# Charger_Control_Board_rev9.net
KiCad netlist of a schematic drawn in EAGLE
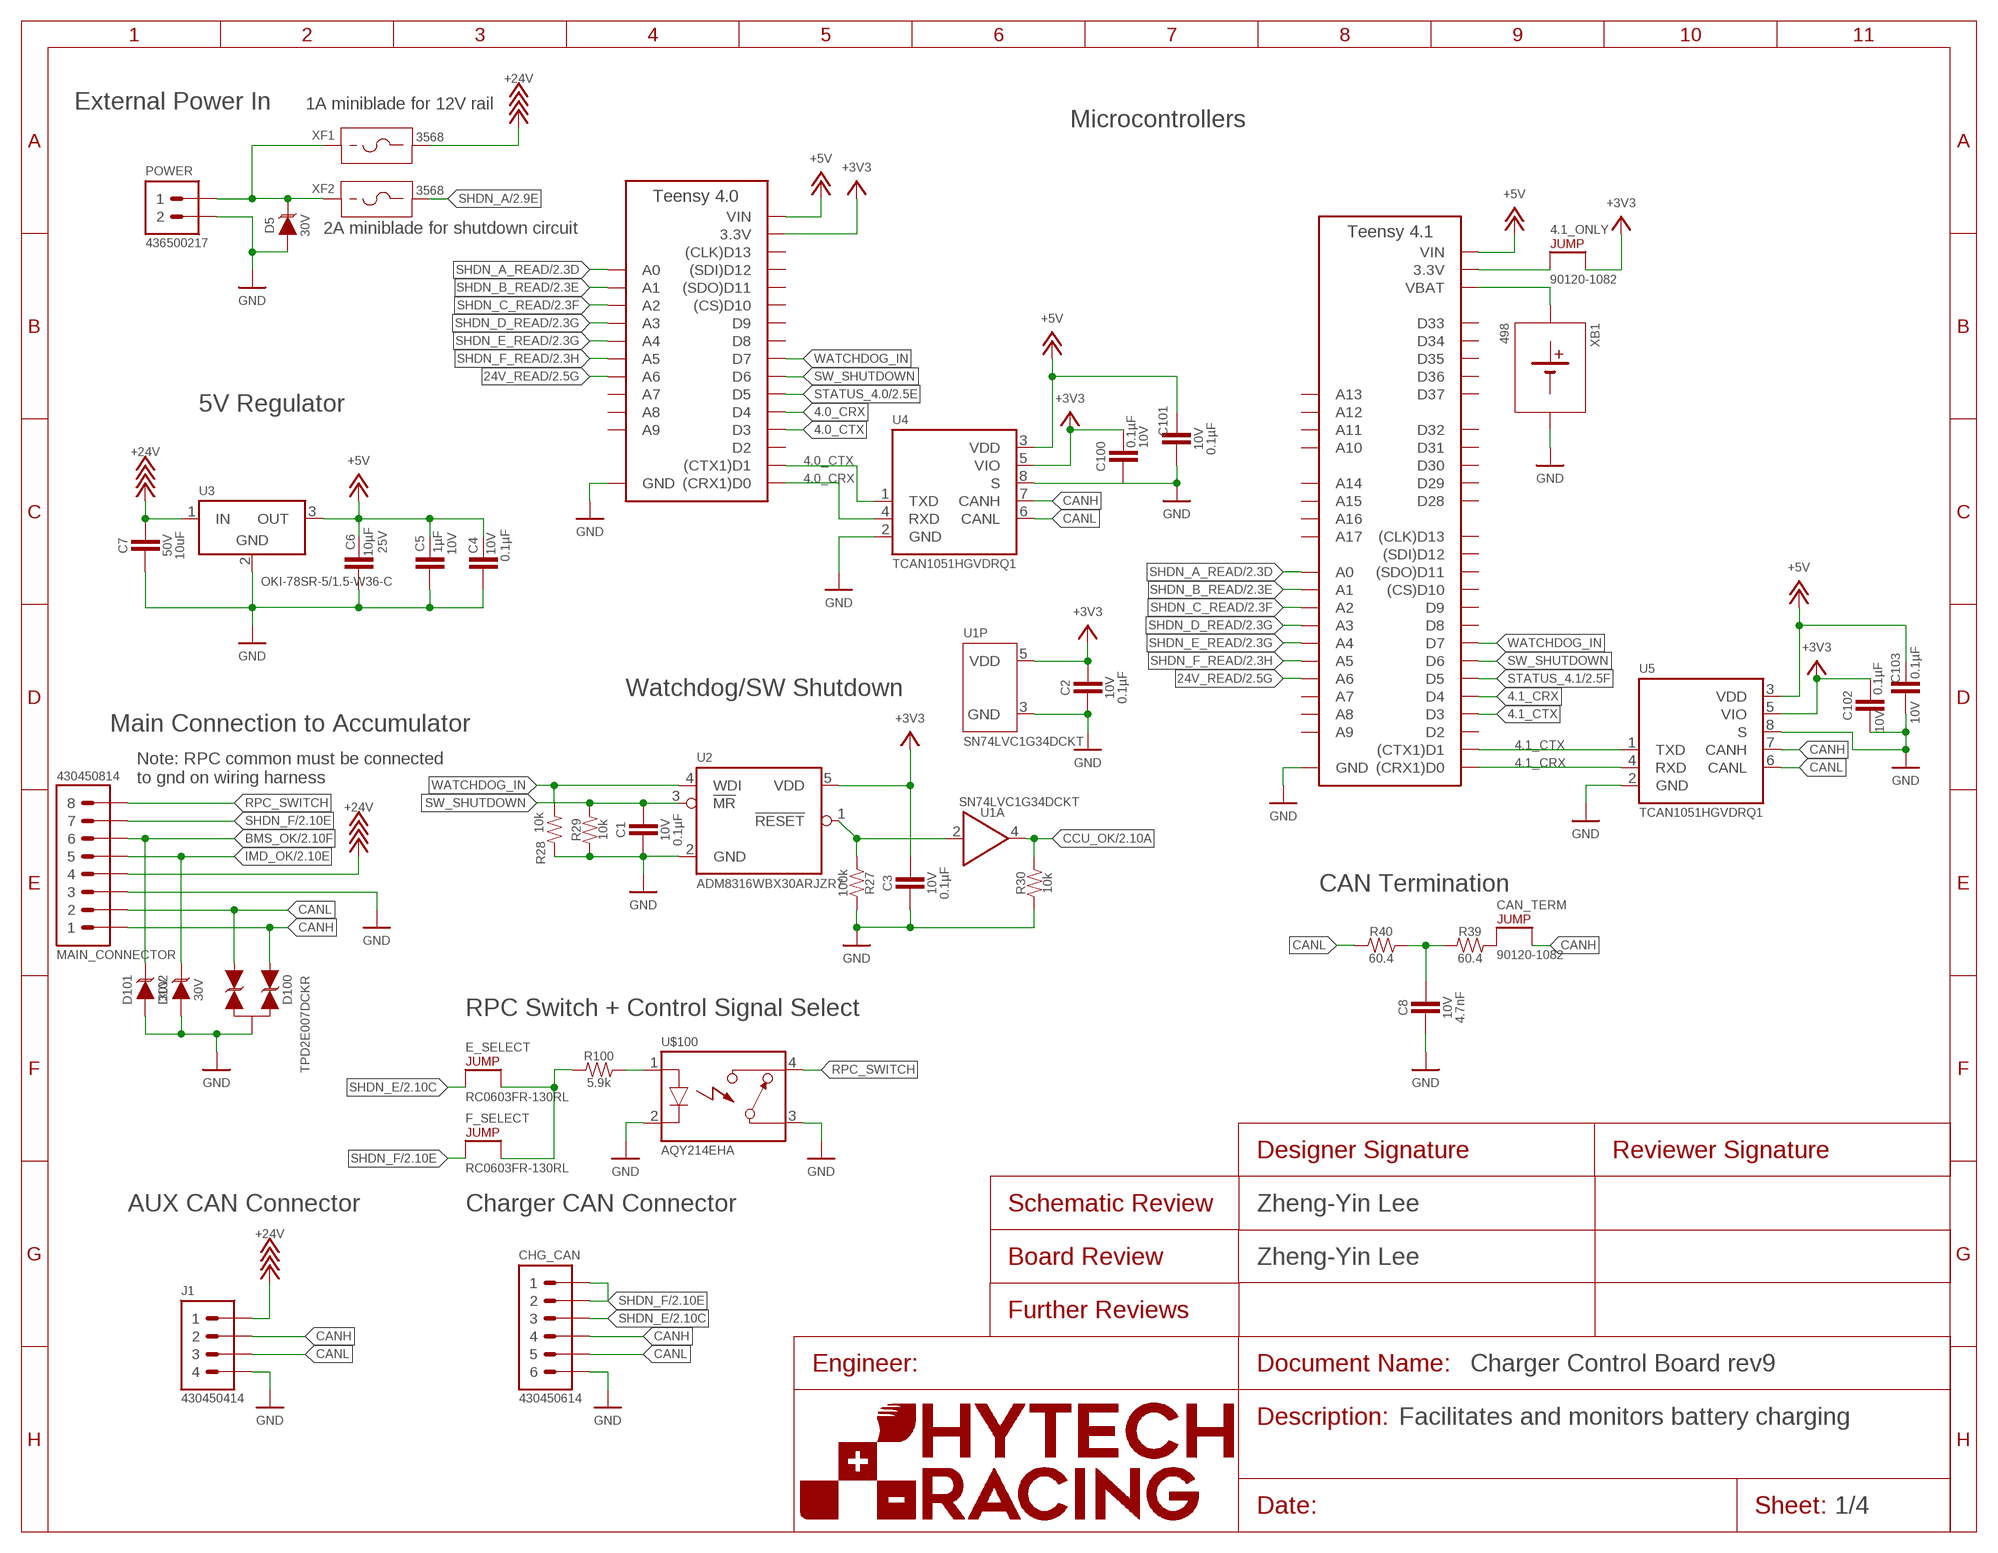
[diagram p0: schematic, sheet 1]
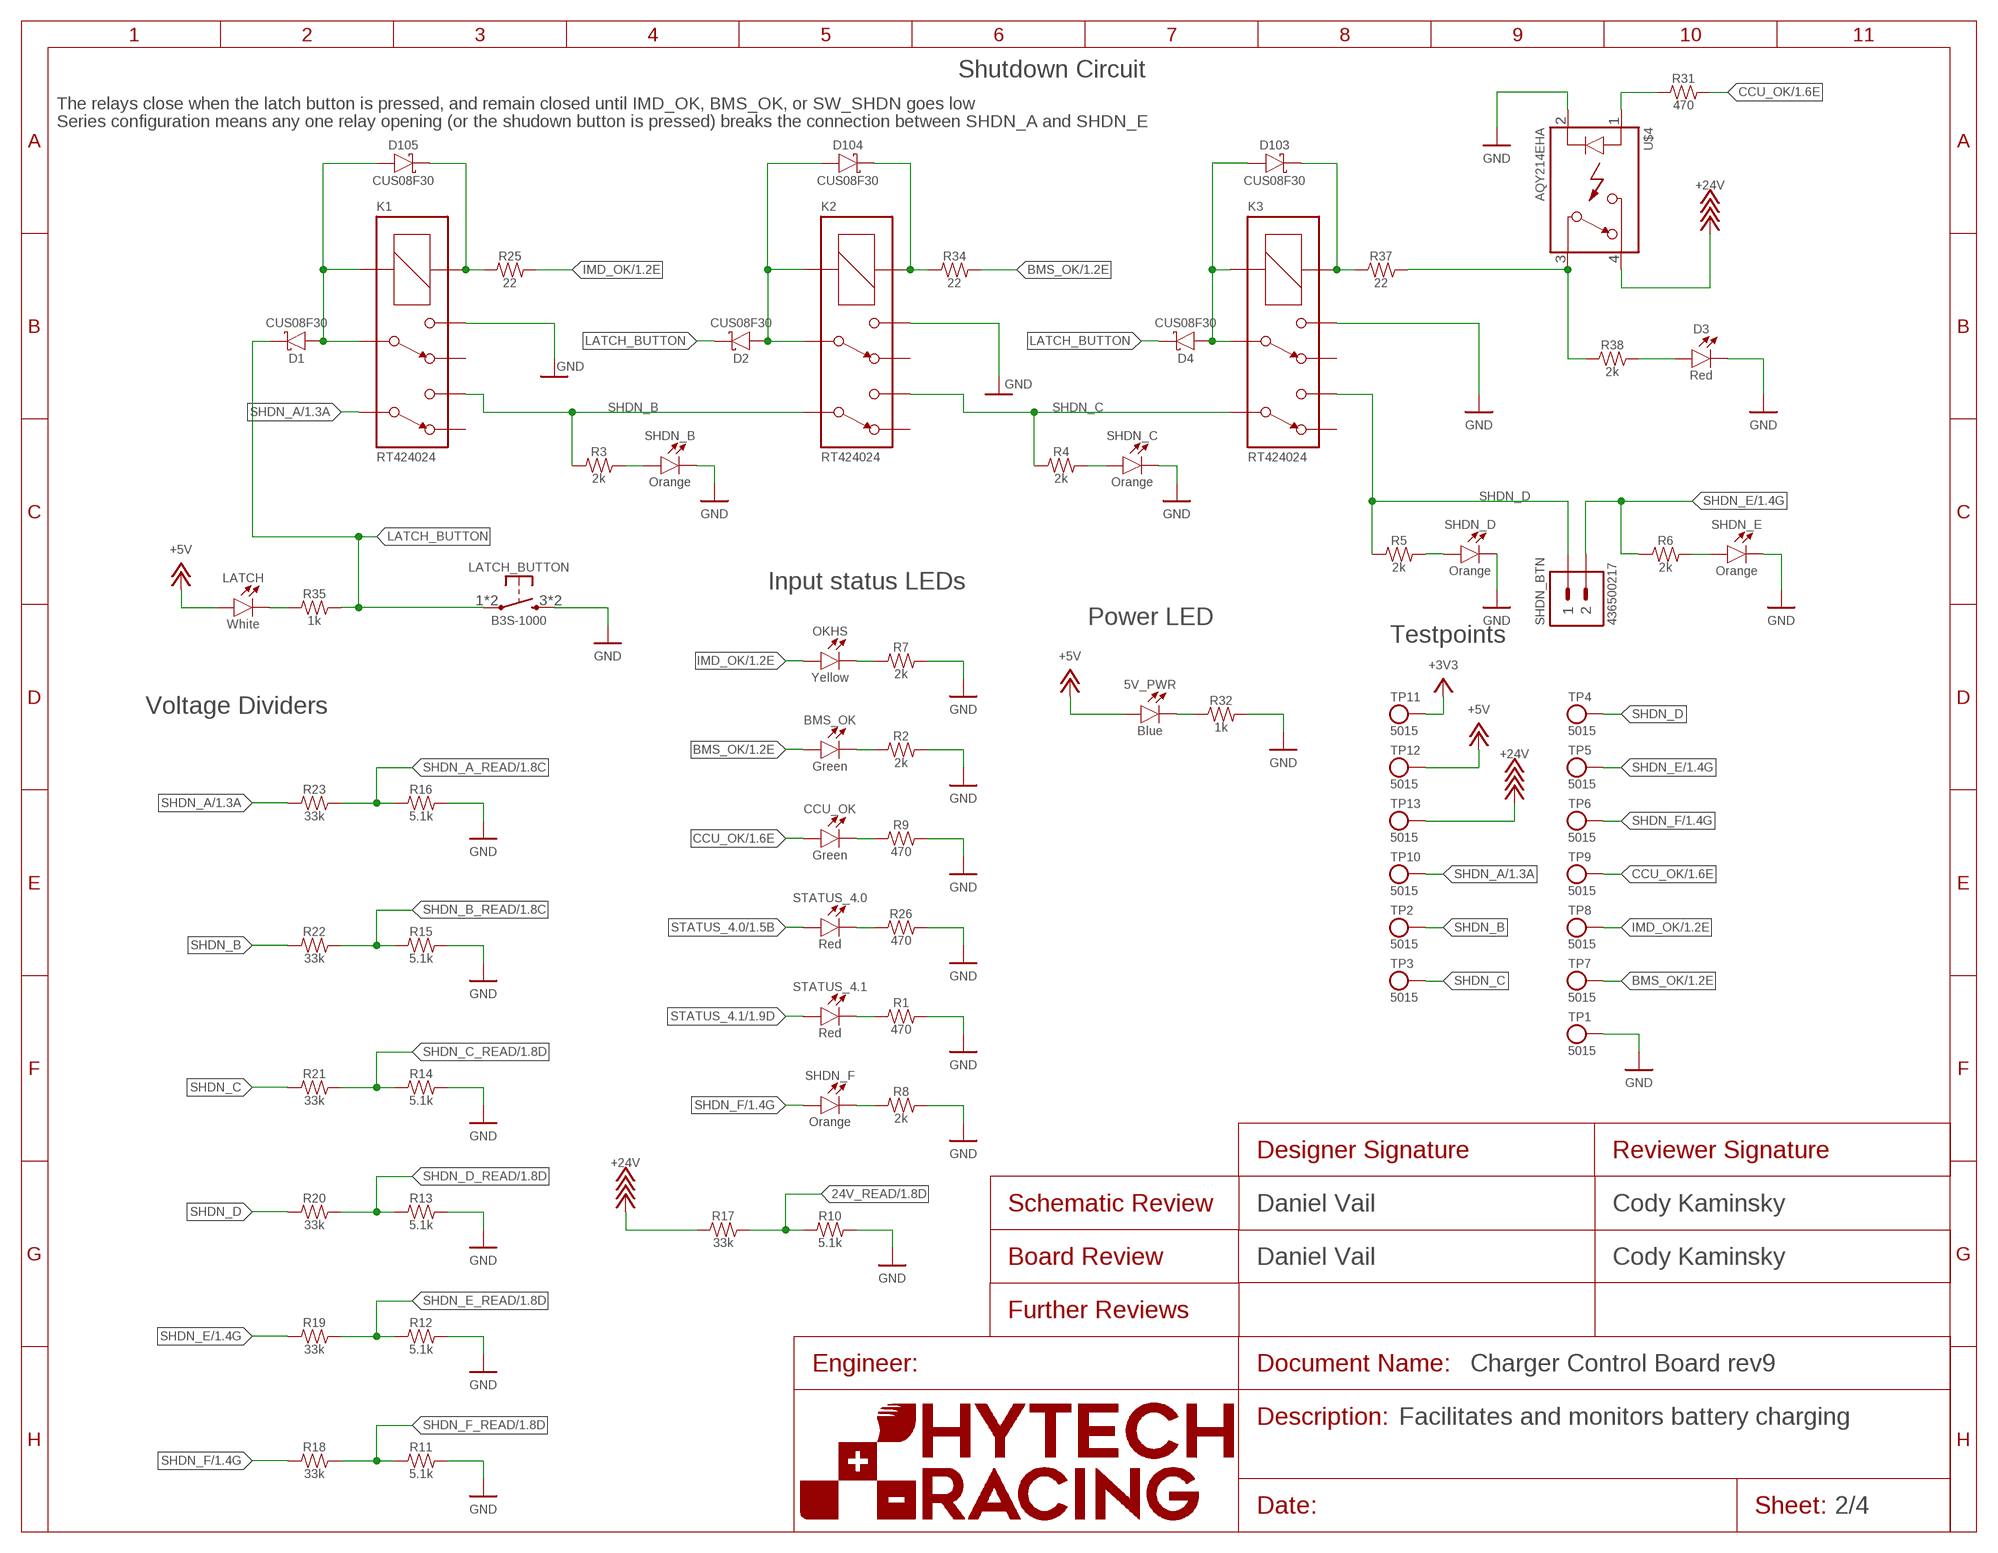
[diagram p1: schematic, sheet 2]
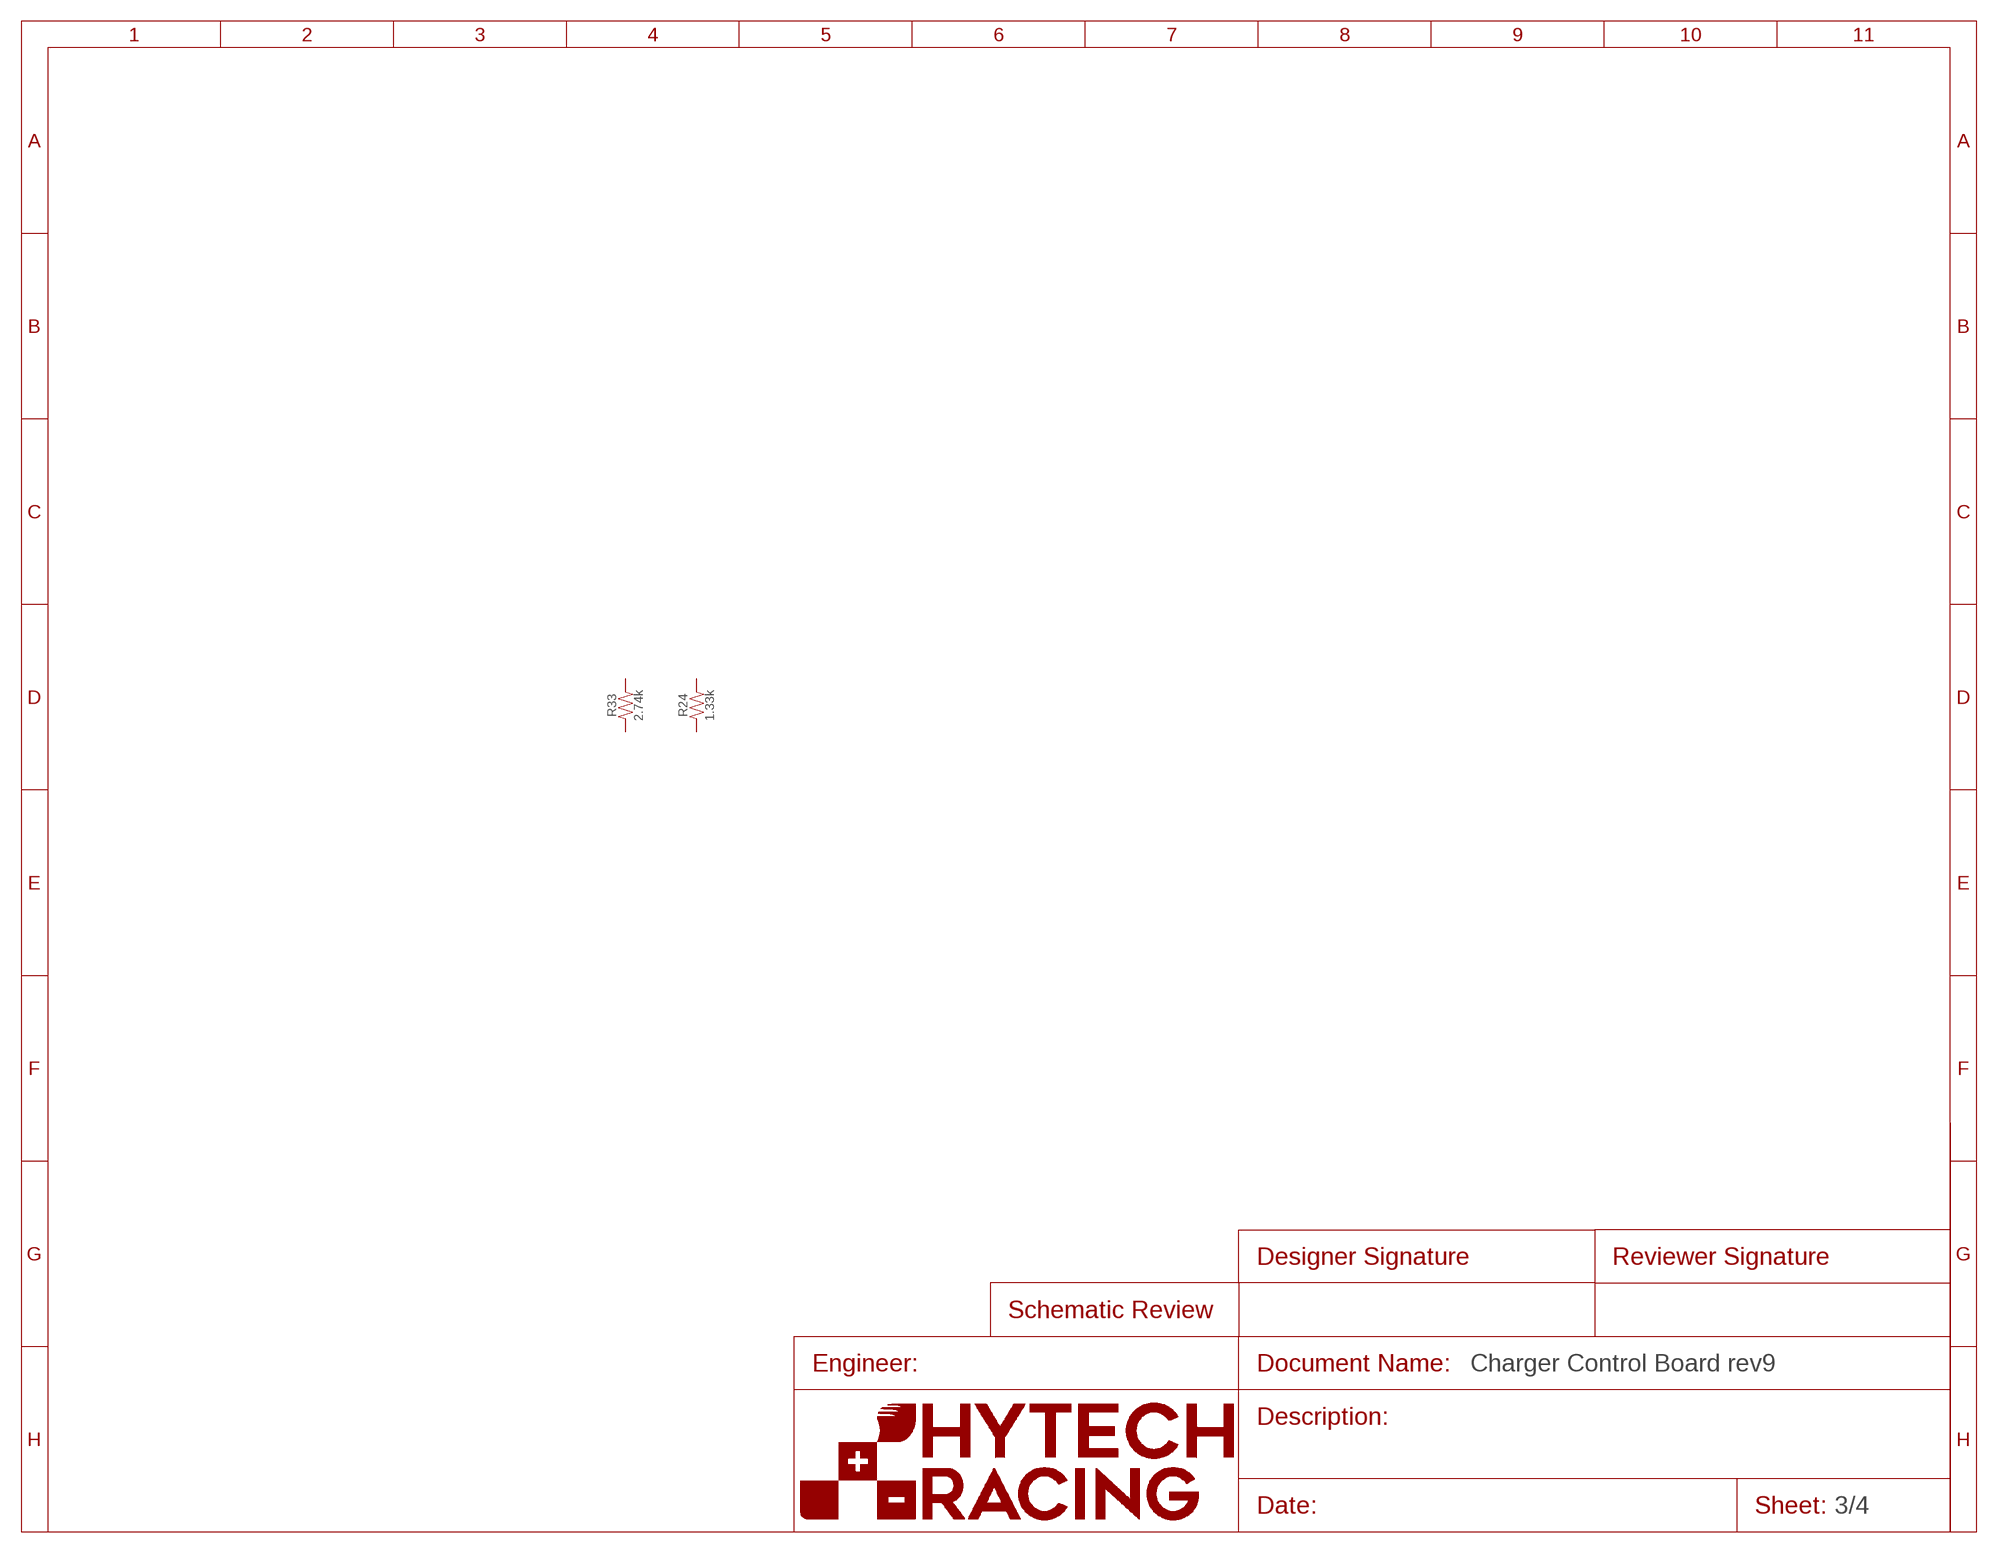
[diagram p2: schematic, sheet 3]
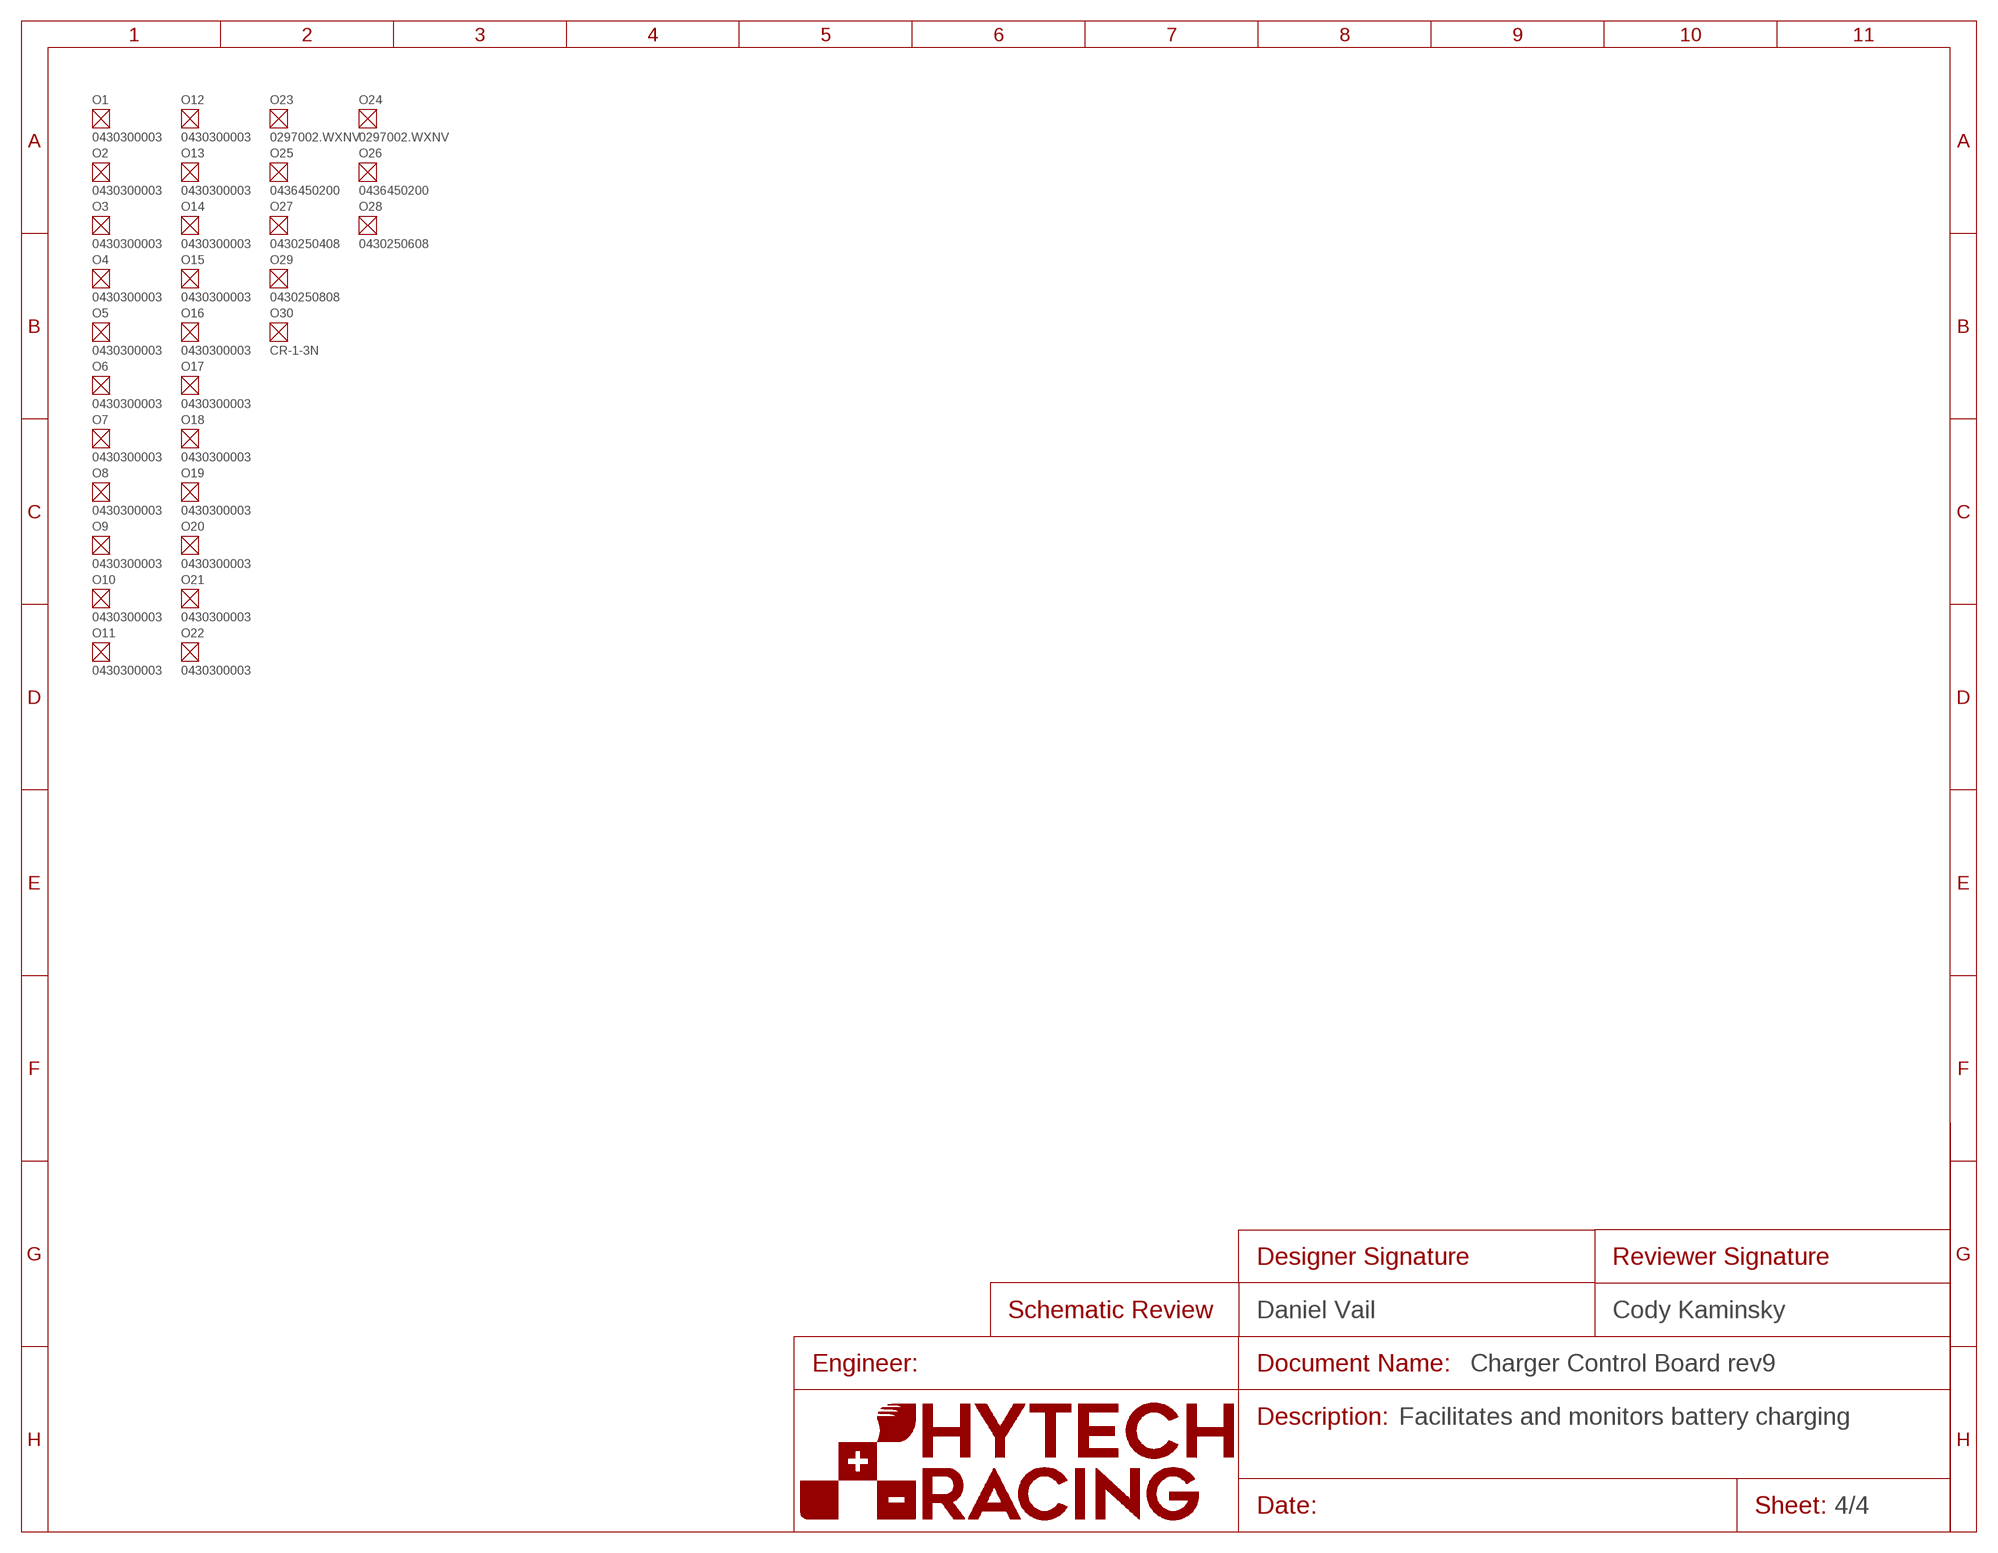
[diagram p3: schematic, sheet 4]

(export (version "E")
  (design (tool "Eeschema 10.0.6"))
  (components
    (comp (ref "4.1_ONLY")
      (value "JUMPER__1X02")
      (footprint "eagle-import:1X02")
      (fields (field (name "MANUFACTURER") "Molex") (field (name "MPN") "90120-1082 "))
      (libsource (lib "eagle-import") (part "JUMPER_?_1X02"))
    )
    (comp (ref "A1")
      (value "TEENSY_4.1")
      (footprint "eagle-import:TEENSY_LONG_EXT")
      (libsource (lib "eagle-import") (part "TEENSY_4.1"))
    )
    (comp (ref "A2")
      (value "TEENSY_4.0TH")
      (footprint "eagle-import:TEENSY_SHORT")
      (libsource (lib "eagle-import") (part "TEENSY_4.0TH"))
    )
    (comp (ref "C1")
      (value "CAPACITOR_0603_10V_0.1UF")
      (footprint "eagle-import:0603-CAP")
      (fields
        (field (name "CAPACITANCE") "0.1µF")
        (field (name "MANUFACTURER") "Vishay Vitramon")
        (field (name "MPN") "VJ0603Y104JXQPW1BC")
        (field (name "TOLERANCE") "5%")
        (field (name "VOLTAGE") "10V")
      )
      (libsource (lib "eagle-import") (part "CAPACITOR_?_060310V_0.1UF"))
    )
    (comp (ref "C2")
      (value "CAPACITOR_0603_10V_0.1UF")
      (footprint "eagle-import:0603-CAP")
      (fields
        (field (name "CAPACITANCE") "0.1µF")
        (field (name "MANUFACTURER") "Vishay Vitramon")
        (field (name "MPN") "VJ0603Y104JXQPW1BC")
        (field (name "TOLERANCE") "5%")
        (field (name "VOLTAGE") "10V")
      )
      (libsource (lib "eagle-import") (part "CAPACITOR_?_060310V_0.1UF"))
    )
    (comp (ref "C3")
      (value "CAPACITOR_0603_10V_0.1UF")
      (footprint "eagle-import:0603-CAP")
      (fields
        (field (name "CAPACITANCE") "0.1µF")
        (field (name "MANUFACTURER") "Vishay Vitramon")
        (field (name "MPN") "VJ0603Y104JXQPW1BC")
        (field (name "TOLERANCE") "5%")
        (field (name "VOLTAGE") "10V")
      )
      (libsource (lib "eagle-import") (part "CAPACITOR_?_060310V_0.1UF"))
    )
    (comp (ref "C4")
      (value "CAPACITOR_0603_10V_0.1UF")
      (footprint "eagle-import:0603-CAP")
      (fields
        (field (name "CAPACITANCE") "0.1µF")
        (field (name "MANUFACTURER") "Vishay Vitramon")
        (field (name "MPN") "VJ0603Y104JXQPW1BC")
        (field (name "TOLERANCE") "5%")
        (field (name "VOLTAGE") "10V")
      )
      (libsource (lib "eagle-import") (part "CAPACITOR_?_060310V_0.1UF"))
    )
    (comp (ref "C5")
      (value "CAPACITOR_0603_10V_1UF")
      (footprint "eagle-import:0603-CAP")
      (fields
        (field (name "CAPACITANCE") "1µF")
        (field (name "MANUFACTURER") "Yageo")
        (field (name "MPN") "CC0603KRX7R6BB105")
        (field (name "TOLERANCE") "10%")
        (field (name "VOLTAGE") "10V")
      )
      (libsource (lib "eagle-import") (part "CAPACITOR_?_060310V_1UF"))
    )
    (comp (ref "C6")
      (value "CAPACITOR_0603_25V_10UF")
      (footprint "eagle-import:0603-CAP")
      (fields
        (field (name "CAPACITANCE") "10µF")
        (field (name "MANUFACTURER") "Murata Electronics")
        (field (name "MPN") "GRM188R61E106MA73D")
        (field (name "TOLERANCE") "20%")
        (field (name "VOLTAGE") "25V")
      )
      (libsource (lib "eagle-import") (part "CAPACITOR_?_060325V_10UF"))
    )
    (comp (ref "C7")
      (value "CAPACITOR_0805_50V_10UF")
      (footprint "eagle-import:0805-CAP")
      (fields
        (field (name "CAPACITANCE") "10uF")
        (field (name "MANUFACTURER") "Murata")
        (field (name "MPN") " GRM21BR61H106KE43L")
        (field (name "TOLERANCE") "10%")
        (field (name "VOLTAGE") "50V")
      )
      (libsource (lib "eagle-import") (part "CAPACITOR_?_080550V_10UF"))
    )
    (comp (ref "C8")
      (value "CAPACITOR_0603_10V_4.7NF")
      (footprint "eagle-import:0603-CAP")
      (fields
        (field (name "CAPACITANCE") "4.7nF")
        (field (name "MANUFACTURER") "Würth Elektronik")
        (field (name "MPN") "885012206012")
        (field (name "TOLERANCE") "10%")
        (field (name "VOLTAGE") "10V")
      )
      (libsource (lib "eagle-import") (part "CAPACITOR_?_060310V_4.7NF"))
    )
    (comp (ref "C100")
      (value "CAPACITOR_0603_10V_0.1UF")
      (footprint "eagle-import:0603-CAP")
      (fields
        (field (name "CAPACITANCE") "0.1µF")
        (field (name "MANUFACTURER") "Vishay Vitramon")
        (field (name "MPN") "VJ0603Y104JXQPW1BC")
        (field (name "TOLERANCE") "5%")
        (field (name "VOLTAGE") "10V")
      )
      (libsource (lib "eagle-import") (part "CAPACITOR_?_060310V_0.1UF"))
    )
    (comp (ref "C101")
      (value "CAPACITOR_0603_10V_0.1UF")
      (footprint "eagle-import:0603-CAP")
      (fields
        (field (name "CAPACITANCE") "0.1µF")
        (field (name "MANUFACTURER") "Vishay Vitramon")
        (field (name "MPN") "VJ0603Y104JXQPW1BC")
        (field (name "TOLERANCE") "5%")
        (field (name "VOLTAGE") "10V")
      )
      (libsource (lib "eagle-import") (part "CAPACITOR_?_060310V_0.1UF"))
    )
    (comp (ref "C102")
      (value "CAPACITOR_0603_10V_0.1UF")
      (footprint "eagle-import:0603-CAP")
      (fields
        (field (name "CAPACITANCE") "0.1µF")
        (field (name "MANUFACTURER") "Vishay Vitramon")
        (field (name "MPN") "VJ0603Y104JXQPW1BC")
        (field (name "TOLERANCE") "5%")
        (field (name "VOLTAGE") "10V")
      )
      (libsource (lib "eagle-import") (part "CAPACITOR_?_060310V_0.1UF"))
    )
    (comp (ref "C103")
      (value "CAPACITOR_0603_10V_0.1UF")
      (footprint "eagle-import:0603-CAP")
      (fields
        (field (name "CAPACITANCE") "0.1µF")
        (field (name "MANUFACTURER") "Vishay Vitramon")
        (field (name "MPN") "VJ0603Y104JXQPW1BC")
        (field (name "TOLERANCE") "5%")
        (field (name "VOLTAGE") "10V")
      )
      (libsource (lib "eagle-import") (part "CAPACITOR_?_060310V_0.1UF"))
    )
    (comp (ref "CAN_TERM")
      (value "JUMPER__1X02")
      (footprint "eagle-import:1X02")
      (fields (field (name "MANUFACTURER") "Molex") (field (name "MPN") "90120-1082 "))
      (libsource (lib "eagle-import") (part "JUMPER_?_1X02"))
    )
    (comp (ref "CHG_CAN")
      (value "CONNECTOR-6_MF_T_V_")
      (footprint "eagle-import:MOLEX_MICROFIT_PTH_VERTICAL_06_DUAL")
      (fields (field (name "MPN") "430450614") (field (name "MANUFACTURER") "MOLEX"))
      (libsource (lib "eagle-import") (part "CONNECTOR-6_?_MF_T_V"))
    )
    (comp (ref "D5")
      (value "TVS_DO-214AA_30V")
      (footprint "eagle-import:DO-214AA")
      (fields
        (field (name "MANUFACTURER") "Bourns Inc.")
        (field (name "MPN") " 1.5SMBJ30A")
        (field (name "VOLTAGE") "30V")
      )
      (libsource (lib "eagle-import") (part "TVS_?_DO-214AA30V"))
    )
    (comp (ref "D100")
      (value "TVS_BIDIRECTIONAL_DUAL")
      (footprint "eagle-import:SC-70-3")
      (fields (field (name "MPN") "TPD2E007DCKR") (field (name "MANUFACTURER") "Texas Instruments"))
      (libsource (lib "eagle-import") (part "TVS_BIDIRECTIONAL_DUAL"))
    )
    (comp (ref "D101")
      (value "TVS_DO-214AA_30V")
      (footprint "eagle-import:DO-214AA")
      (fields
        (field (name "MANUFACTURER") "Bourns Inc.")
        (field (name "MPN") " 1.5SMBJ30A")
        (field (name "VOLTAGE") "30V")
      )
      (libsource (lib "eagle-import") (part "TVS_?_DO-214AA30V"))
    )
    (comp (ref "D102")
      (value "TVS_DO-214AA_30V")
      (footprint "eagle-import:DO-214AA")
      (fields
        (field (name "MANUFACTURER") "Bourns Inc.")
        (field (name "MPN") " 1.5SMBJ30A")
        (field (name "VOLTAGE") "30V")
      )
      (libsource (lib "eagle-import") (part "TVS_?_DO-214AA30V"))
    )
    (comp (ref "E_SELECT")
      (value "JUMPER_0603_")
      (footprint "eagle-import:0603-RES")
      (fields (field (name "MPN") "RC0603FR-130RL") (field (name "MANUFACTURER") "YAGEO"))
      (libsource (lib "eagle-import") (part "JUMPER_?_0603"))
    )
    (comp (ref "F_SELECT")
      (value "JUMPER_0603_")
      (footprint "eagle-import:0603-RES")
      (fields (field (name "MPN") "RC0603FR-130RL") (field (name "MANUFACTURER") "YAGEO"))
      (libsource (lib "eagle-import") (part "JUMPER_?_0603"))
    )
    (comp (ref "J1")
      (value "CONNECTOR-4_μF_T_V_BLACK")
      (footprint "eagle-import:MOLEX_MICROFIT_PTH_VERTICAL_04_DUAL")
      (fields (field (name "MANUFACTURER") "Molex") (field (name "MPN") "430450414"))
      (libsource (lib "eagle-import") (part "CONNECTOR-4_?_μF_T_VBLACK"))
    )
    (comp (ref "MAIN_CONNECTOR")
      (value "CONNECTOR-8_MF_T_V_")
      (footprint "eagle-import:MOLEX_MICROFIT_PTH_VERTICAL_08_DUAL")
      (fields (field (name "MPN") "430450814") (field (name "MANUFACTURER") "MOLEX"))
      (libsource (lib "eagle-import") (part "CONNECTOR-8_?_MF_T_V"))
    )
    (comp (ref "POWER")
      (value "CONNECTOR-2_μF_T_V_")
      (footprint "eagle-import:MOLEX_MICROFIT_PTH_VERTICAL_02_DUAL")
      (fields (field (name "MANUFACTURER") "Molex") (field (name "MPN") "436500217"))
      (libsource (lib "eagle-import") (part "CONNECTOR-2_?_μF_T_VBLACK"))
    )
    (comp (ref "R27")
      (value "RESISTOR_0603_100K")
      (footprint "eagle-import:0603-RES")
      (fields
        (field (name "MANUFACTURER") "Yageo")
        (field (name "MPN") "RC0603FR-07100KL")
        (field (name "POWER") "0.1W")
        (field (name "RESISTANCE") "100k")
      )
      (libsource (lib "eagle-import") (part "RESISTOR_?_0603100K"))
    )
    (comp (ref "R28")
      (value "RESISTOR_0603_10K")
      (footprint "eagle-import:0603-RES")
      (fields
        (field (name "MANUFACTURER") "Panasonic Electronic Components")
        (field (name "MPN") "ERA-3ARB103V")
        (field (name "POWER") "0.1W")
        (field (name "RESISTANCE") "10k")
      )
      (libsource (lib "eagle-import") (part "RESISTOR_?_060310K"))
    )
    (comp (ref "R29")
      (value "RESISTOR_0603_10K")
      (footprint "eagle-import:0603-RES")
      (fields
        (field (name "MANUFACTURER") "Panasonic Electronic Components")
        (field (name "MPN") "ERA-3ARB103V")
        (field (name "POWER") "0.1W")
        (field (name "RESISTANCE") "10k")
      )
      (libsource (lib "eagle-import") (part "RESISTOR_?_060310K"))
    )
    (comp (ref "R30")
      (value "RESISTOR_0603_10K")
      (footprint "eagle-import:0603-RES")
      (fields
        (field (name "MANUFACTURER") "Panasonic Electronic Components")
        (field (name "MPN") "ERA-3ARB103V")
        (field (name "POWER") "0.1W")
        (field (name "RESISTANCE") "10k")
      )
      (libsource (lib "eagle-import") (part "RESISTOR_?_060310K"))
    )
    (comp (ref "R39")
      (value "RESISTOR_0603_60.4")
      (footprint "eagle-import:0603-RES")
      (fields
        (field (name "MANUFACTURER") "Yageo")
        (field (name "MPN") "RC0603FR-0760R4L")
        (field (name "POWER") "0.1W")
        (field (name "RESISTANCE") "60.4")
      )
      (libsource (lib "eagle-import") (part "RESISTOR_?_060360.4"))
    )
    (comp (ref "R40")
      (value "RESISTOR_0603_60.4")
      (footprint "eagle-import:0603-RES")
      (fields
        (field (name "MANUFACTURER") "Yageo")
        (field (name "MPN") "RC0603FR-0760R4L")
        (field (name "POWER") "0.1W")
        (field (name "RESISTANCE") "60.4")
      )
      (libsource (lib "eagle-import") (part "RESISTOR_?_060360.4"))
    )
    (comp (ref "R100")
      (value "RESISTOR_0603_5.9K")
      (footprint "eagle-import:0603-RES")
      (fields
        (field (name "MANUFACTURER") "Panasonic Electronic Components")
        (field (name "MPN") "ERA-3AEB5901V")
        (field (name "POWER") "0.1W")
        (field (name "RESISTANCE") "5.9k")
      )
      (libsource (lib "eagle-import") (part "RESISTOR_?_06035.9K"))
    )
    (comp (ref "U$100")
      (value "RELAY_SOLIDSTATE_NO_DIP-4")
      (footprint "eagle-import:DIP-4")
      (fields (field (name "MPN") "AQY214EHA") (field (name "MANUFACTURER") "Panasonic"))
      (libsource (lib "eagle-import") (part "RELAY_SOLIDSTATE_NO_DIP-4"))
    )
    (comp (ref "U1")
      (value "LOGICGATE_BUFFER")
      (footprint "eagle-import:SC-70-5")
      (fields (field (name "MANUFACTURER") "Texas Instruments"))
      (libsource (lib "eagle-import") (part "LOGICGATE_BUFFER"))
    )
    (comp (ref "U2")
      (value "ADM8316WBX30")
      (footprint "eagle-import:SOT-23-5")
      (fields (field (name "MANUFACTURER") "Analog Devices Inc.") (field (name "MPN") "ADM8316WBX30ARJZR7"))
      (libsource (lib "eagle-import") (part "ADM8316WBX30"))
    )
    (comp (ref "U3")
      (value "VOLTAGE_REGULATOR_MODULE_OKI-78SR_5V")
      (footprint "eagle-import:OKI-78SR")
      (fields
        (field (name "MANUFACTURER") "Murata Power Solutions Inc.")
        (field (name "MPN") "OKI-78SR-5/1.5-W36-C")
      )
      (libsource (lib "eagle-import") (part "VOLTAGE_REGULATOR_MODULE_?_OKI-78SR5V"))
    )
    (comp (ref "U4")
      (value "TCAN1051HQV-Q1")
      (footprint "eagle-import:SOIC-08(NARROW,0.15_)")
      (fields (field (name "MANUFACTURER") "Texas Instruments") (field (name "MPN") "TCAN1051HGVDRQ1"))
      (libsource (lib "eagle-import") (part "TCAN1051V-Q1HQ"))
    )
    (comp (ref "U5")
      (value "TCAN1051HQV-Q1")
      (footprint "eagle-import:SOIC-08(NARROW,0.15_)")
      (fields (field (name "MANUFACTURER") "Texas Instruments") (field (name "MPN") "TCAN1051HGVDRQ1"))
      (libsource (lib "eagle-import") (part "TCAN1051V-Q1HQ"))
    )
    (comp (ref "XB1")
      (value "BATTERY_HOLDER_KEYSTONE_498")
      (footprint "eagle-import:498")
      (fields (field (name "MPN") "498") (field (name "MANUFACTURER") "Keystone Electronics"))
      (libsource (lib "eagle-import") (part "BATTERY_HOLDER_KEYSTONE_498"))
    )
    (comp (ref "XF1")
      (value "FUSE_HOLDER_MINIBLADEPTH")
      (footprint "eagle-import:3568")
      (fields (field (name "MANUFACTURER") "Keystone") (field (name "MPN") "3568"))
      (libsource (lib "eagle-import") (part "FUSE_HOLDER_PTHMINIBLADE"))
    )
    (comp (ref "XF2")
      (value "FUSE_HOLDER_MINIBLADEPTH")
      (footprint "eagle-import:3568")
      (fields (field (name "MANUFACTURER") "Keystone") (field (name "MPN") "3568"))
      (libsource (lib "eagle-import") (part "FUSE_HOLDER_PTHMINIBLADE"))
    )
    (comp (ref "5V_PWR")
      (value "LED_0603_BLUE")
      (footprint "eagle-import:0603-LED")
      (fields
        (field (name "COLOR") "Blue")
        (field (name "MANUFACTURER") "Kingbright")
        (field (name "MPN") "APT1608VBC/D")
      )
      (libsource (lib "eagle-import") (part "LED_?_0603BLUE"))
    )
    (comp (ref "BMS_OK")
      (value "LED_0603_GREEN")
      (footprint "eagle-import:0603-LED")
      (fields
        (field (name "COLOR") "Green")
        (field (name "MANUFACTURER") "Kingbright")
        (field (name "MPN") "APT1608ZGCK")
      )
      (libsource (lib "eagle-import") (part "LED_?_0603GREEN"))
    )
    (comp (ref "CCU_OK")
      (value "LED_0603_GREEN")
      (footprint "eagle-import:0603-LED")
      (fields
        (field (name "COLOR") "Green")
        (field (name "MANUFACTURER") "Kingbright")
        (field (name "MPN") "APT1608ZGCK")
      )
      (libsource (lib "eagle-import") (part "LED_?_0603GREEN"))
    )
    (comp (ref "D1")
      (value "SCHOTTKY_SOD323_30V")
      (footprint "eagle-import:SOD-323")
      (fields
        (field (name "MANUFACTURER") "Toshiba Semiconductor and Storage")
        (field (name "MPN") "CUS08F30")
        (field (name "VOLTAGE") "30V")
      )
      (libsource (lib "eagle-import") (part "SCHOTTKY_?_SOD32330V"))
    )
    (comp (ref "D2")
      (value "SCHOTTKY_SOD323_30V")
      (footprint "eagle-import:SOD-323")
      (fields
        (field (name "MANUFACTURER") "Toshiba Semiconductor and Storage")
        (field (name "MPN") "CUS08F30")
        (field (name "VOLTAGE") "30V")
      )
      (libsource (lib "eagle-import") (part "SCHOTTKY_?_SOD32330V"))
    )
    (comp (ref "D3")
      (value "LED_0603_RED")
      (footprint "eagle-import:0603-LED")
      (fields
        (field (name "COLOR") "Red")
        (field (name "MANUFACTURER") "Kingbright")
        (field (name "MPN") "APT1608SECK/J3-PRV")
      )
      (libsource (lib "eagle-import") (part "LED_?_0603RED"))
    )
    (comp (ref "D4")
      (value "SCHOTTKY_SOD323_30V")
      (footprint "eagle-import:SOD-323")
      (fields
        (field (name "MANUFACTURER") "Toshiba Semiconductor and Storage")
        (field (name "MPN") "CUS08F30")
        (field (name "VOLTAGE") "30V")
      )
      (libsource (lib "eagle-import") (part "SCHOTTKY_?_SOD32330V"))
    )
    (comp (ref "D103")
      (value "SCHOTTKY_SOD323_30V")
      (footprint "eagle-import:SOD-323")
      (fields
        (field (name "MANUFACTURER") "Toshiba Semiconductor and Storage")
        (field (name "MPN") "CUS08F30")
        (field (name "VOLTAGE") "30V")
      )
      (libsource (lib "eagle-import") (part "SCHOTTKY_?_SOD32330V"))
    )
    (comp (ref "D104")
      (value "SCHOTTKY_SOD323_30V")
      (footprint "eagle-import:SOD-323")
      (fields
        (field (name "MANUFACTURER") "Toshiba Semiconductor and Storage")
        (field (name "MPN") "CUS08F30")
        (field (name "VOLTAGE") "30V")
      )
      (libsource (lib "eagle-import") (part "SCHOTTKY_?_SOD32330V"))
    )
    (comp (ref "D105")
      (value "SCHOTTKY_SOD323_30V")
      (footprint "eagle-import:SOD-323")
      (fields
        (field (name "MANUFACTURER") "Toshiba Semiconductor and Storage")
        (field (name "MPN") "CUS08F30")
        (field (name "VOLTAGE") "30V")
      )
      (libsource (lib "eagle-import") (part "SCHOTTKY_?_SOD32330V"))
    )
    (comp (ref "K1")
      (value "RELAY_DPDT_RT424024TH")
      (footprint "eagle-import:RT_2_")
      (fields (field (name "MANUFACTURER") "TE Connectivity") (field (name "MPN") "RT424024"))
      (libsource (lib "eagle-import") (part "RELAY_DPDT_THRT424024"))
    )
    (comp (ref "K2")
      (value "RELAY_DPDT_RT424024TH")
      (footprint "eagle-import:RT_2_")
      (fields (field (name "MANUFACTURER") "TE Connectivity") (field (name "MPN") "RT424024"))
      (libsource (lib "eagle-import") (part "RELAY_DPDT_THRT424024"))
    )
    (comp (ref "K3")
      (value "RELAY_DPDT_RT424024TH")
      (footprint "eagle-import:RT_2_")
      (fields (field (name "MANUFACTURER") "TE Connectivity") (field (name "MPN") "RT424024"))
      (libsource (lib "eagle-import") (part "RELAY_DPDT_THRT424024"))
    )
    (comp (ref "LATCH")
      (value "LED_0603_WHITE")
      (footprint "eagle-import:0603-LED")
      (fields
        (field (name "COLOR") "White")
        (field (name "MANUFACTURER") "Bivar Inc.")
        (field (name "MPN") "SM0603UWC")
      )
      (libsource (lib "eagle-import") (part "LED_?_0603WHITE"))
    )
    (comp (ref "LATCH_BUTTON")
      (value "BUTTON")
      (footprint "eagle-import:B3S-100X")
      (fields (field (name "MPN") "B3S-1000") (field (name "MANUFACTURER") "Omron"))
      (libsource (lib "eagle-import") (part "BUTTON"))
    )
    (comp (ref "OKHS")
      (value "LED_0603_YELLOW")
      (footprint "eagle-import:0603-LED")
      (fields
        (field (name "COLOR") "Yellow")
        (field (name "MANUFACTURER") "Kingbright")
        (field (name "MPN") "APT1608SYCK/J3-PRV")
      )
      (libsource (lib "eagle-import") (part "LED_?_0603YELLOW"))
    )
    (comp (ref "R1")
      (value "RESISTOR_0603_470")
      (footprint "eagle-import:0603-RES")
      (fields
        (field (name "MANUFACTURER") "Panasonic Electronic Components")
        (field (name "MPN") "ERJ-PA3F4700V")
        (field (name "POWER") "0.25W")
        (field (name "RESISTANCE") "470")
      )
      (libsource (lib "eagle-import") (part "RESISTOR_?_0603470"))
    )
    (comp (ref "R2")
      (value "RESISTOR_0603_2K")
      (footprint "eagle-import:0603-RES")
      (fields
        (field (name "MANUFACTURER") "Panasonic Electronic Components")
        (field (name "MPN") "ERJ-UP3F2001V")
        (field (name "POWER") "0.25W")
        (field (name "RESISTANCE") "2k")
      )
      (libsource (lib "eagle-import") (part "RESISTOR_?_06032K"))
    )
    (comp (ref "R3")
      (value "RESISTOR_0603_2K")
      (footprint "eagle-import:0603-RES")
      (fields
        (field (name "MANUFACTURER") "Panasonic Electronic Components")
        (field (name "MPN") "ERJ-UP3F2001V")
        (field (name "POWER") "0.25W")
        (field (name "RESISTANCE") "2k")
      )
      (libsource (lib "eagle-import") (part "RESISTOR_?_06032K"))
    )
    (comp (ref "R4")
      (value "RESISTOR_0603_2K")
      (footprint "eagle-import:0603-RES")
      (fields
        (field (name "MANUFACTURER") "Panasonic Electronic Components")
        (field (name "MPN") "ERJ-UP3F2001V")
        (field (name "POWER") "0.25W")
        (field (name "RESISTANCE") "2k")
      )
      (libsource (lib "eagle-import") (part "RESISTOR_?_06032K"))
    )
    (comp (ref "R5")
      (value "RESISTOR_0603_2K")
      (footprint "eagle-import:0603-RES")
      (fields
        (field (name "MANUFACTURER") "Panasonic Electronic Components")
        (field (name "MPN") "ERJ-UP3F2001V")
        (field (name "POWER") "0.25W")
        (field (name "RESISTANCE") "2k")
      )
      (libsource (lib "eagle-import") (part "RESISTOR_?_06032K"))
    )
    (comp (ref "R6")
      (value "RESISTOR_0603_2K")
      (footprint "eagle-import:0603-RES")
      (fields
        (field (name "MANUFACTURER") "Panasonic Electronic Components")
        (field (name "MPN") "ERJ-UP3F2001V")
        (field (name "POWER") "0.25W")
        (field (name "RESISTANCE") "2k")
      )
      (libsource (lib "eagle-import") (part "RESISTOR_?_06032K"))
    )
    (comp (ref "R7")
      (value "RESISTOR_0603_2K")
      (footprint "eagle-import:0603-RES")
      (fields
        (field (name "MANUFACTURER") "Panasonic Electronic Components")
        (field (name "MPN") "ERJ-UP3F2001V")
        (field (name "POWER") "0.25W")
        (field (name "RESISTANCE") "2k")
      )
      (libsource (lib "eagle-import") (part "RESISTOR_?_06032K"))
    )
    (comp (ref "R8")
      (value "RESISTOR_0603_2K")
      (footprint "eagle-import:0603-RES")
      (fields
        (field (name "MANUFACTURER") "Panasonic Electronic Components")
        (field (name "MPN") "ERJ-UP3F2001V")
        (field (name "POWER") "0.25W")
        (field (name "RESISTANCE") "2k")
      )
      (libsource (lib "eagle-import") (part "RESISTOR_?_06032K"))
    )
    (comp (ref "R9")
      (value "RESISTOR_0603_470")
      (footprint "eagle-import:0603-RES")
      (fields
        (field (name "MANUFACTURER") "Panasonic Electronic Components")
        (field (name "MPN") "ERJ-PA3F4700V")
        (field (name "POWER") "0.25W")
        (field (name "RESISTANCE") "470")
      )
      (libsource (lib "eagle-import") (part "RESISTOR_?_0603470"))
    )
    (comp (ref "R10")
      (value "RESISTOR_0603_5.1K")
      (footprint "eagle-import:0603-RES")
      (fields
        (field (name "MANUFACTURER") "Yageo")
        (field (name "MPN") "RC0603FR-075K1L")
        (field (name "POWER") "0.1W")
        (field (name "RESISTANCE") "5.1k")
      )
      (libsource (lib "eagle-import") (part "RESISTOR_?_06035.1K"))
    )
    (comp (ref "R11")
      (value "RESISTOR_0603_5.1K")
      (footprint "eagle-import:0603-RES")
      (fields
        (field (name "MANUFACTURER") "Yageo")
        (field (name "MPN") "RC0603FR-075K1L")
        (field (name "POWER") "0.1W")
        (field (name "RESISTANCE") "5.1k")
      )
      (libsource (lib "eagle-import") (part "RESISTOR_?_06035.1K"))
    )
    (comp (ref "R12")
      (value "RESISTOR_0603_5.1K")
      (footprint "eagle-import:0603-RES")
      (fields
        (field (name "MANUFACTURER") "Yageo")
        (field (name "MPN") "RC0603FR-075K1L")
        (field (name "POWER") "0.1W")
        (field (name "RESISTANCE") "5.1k")
      )
      (libsource (lib "eagle-import") (part "RESISTOR_?_06035.1K"))
    )
    (comp (ref "R13")
      (value "RESISTOR_0603_5.1K")
      (footprint "eagle-import:0603-RES")
      (fields
        (field (name "MANUFACTURER") "Yageo")
        (field (name "MPN") "RC0603FR-075K1L")
        (field (name "POWER") "0.1W")
        (field (name "RESISTANCE") "5.1k")
      )
      (libsource (lib "eagle-import") (part "RESISTOR_?_06035.1K"))
    )
    (comp (ref "R14")
      (value "RESISTOR_0603_5.1K")
      (footprint "eagle-import:0603-RES")
      (fields
        (field (name "MANUFACTURER") "Yageo")
        (field (name "MPN") "RC0603FR-075K1L")
        (field (name "POWER") "0.1W")
        (field (name "RESISTANCE") "5.1k")
      )
      (libsource (lib "eagle-import") (part "RESISTOR_?_06035.1K"))
    )
    (comp (ref "R15")
      (value "RESISTOR_0603_5.1K")
      (footprint "eagle-import:0603-RES")
      (fields
        (field (name "MANUFACTURER") "Yageo")
        (field (name "MPN") "RC0603FR-075K1L")
        (field (name "POWER") "0.1W")
        (field (name "RESISTANCE") "5.1k")
      )
      (libsource (lib "eagle-import") (part "RESISTOR_?_06035.1K"))
    )
    (comp (ref "R16")
      (value "RESISTOR_0603_5.1K")
      (footprint "eagle-import:0603-RES")
      (fields
        (field (name "MANUFACTURER") "Yageo")
        (field (name "MPN") "RC0603FR-075K1L")
        (field (name "POWER") "0.1W")
        (field (name "RESISTANCE") "5.1k")
      )
      (libsource (lib "eagle-import") (part "RESISTOR_?_06035.1K"))
    )
    (comp (ref "R17")
      (value "RESISTOR_0603_33K")
      (footprint "eagle-import:0603-RES")
      (fields
        (field (name "MANUFACTURER") "Rohm Semiconductor")
        (field (name "MPN") "KTR03EZPF3302")
        (field (name "POWER") "0.1W")
        (field (name "RESISTANCE") "33k")
      )
      (libsource (lib "eagle-import") (part "RESISTOR_?_060333K"))
    )
    (comp (ref "R18")
      (value "RESISTOR_0603_33K")
      (footprint "eagle-import:0603-RES")
      (fields
        (field (name "MANUFACTURER") "Rohm Semiconductor")
        (field (name "MPN") "KTR03EZPF3302")
        (field (name "POWER") "0.1W")
        (field (name "RESISTANCE") "33k")
      )
      (libsource (lib "eagle-import") (part "RESISTOR_?_060333K"))
    )
    (comp (ref "R19")
      (value "RESISTOR_0603_33K")
      (footprint "eagle-import:0603-RES")
      (fields
        (field (name "MANUFACTURER") "Rohm Semiconductor")
        (field (name "MPN") "KTR03EZPF3302")
        (field (name "POWER") "0.1W")
        (field (name "RESISTANCE") "33k")
      )
      (libsource (lib "eagle-import") (part "RESISTOR_?_060333K"))
    )
    (comp (ref "R20")
      (value "RESISTOR_0603_33K")
      (footprint "eagle-import:0603-RES")
      (fields
        (field (name "MANUFACTURER") "Rohm Semiconductor")
        (field (name "MPN") "KTR03EZPF3302")
        (field (name "POWER") "0.1W")
        (field (name "RESISTANCE") "33k")
      )
      (libsource (lib "eagle-import") (part "RESISTOR_?_060333K"))
    )
    (comp (ref "R21")
      (value "RESISTOR_0603_33K")
      (footprint "eagle-import:0603-RES")
      (fields
        (field (name "MANUFACTURER") "Rohm Semiconductor")
        (field (name "MPN") "KTR03EZPF3302")
        (field (name "POWER") "0.1W")
        (field (name "RESISTANCE") "33k")
      )
      (libsource (lib "eagle-import") (part "RESISTOR_?_060333K"))
    )
    (comp (ref "R22")
      (value "RESISTOR_0603_33K")
      (footprint "eagle-import:0603-RES")
      (fields
        (field (name "MANUFACTURER") "Rohm Semiconductor")
        (field (name "MPN") "KTR03EZPF3302")
        (field (name "POWER") "0.1W")
        (field (name "RESISTANCE") "33k")
      )
      (libsource (lib "eagle-import") (part "RESISTOR_?_060333K"))
    )
    (comp (ref "R23")
      (value "RESISTOR_0603_33K")
      (footprint "eagle-import:0603-RES")
      (fields
        (field (name "MANUFACTURER") "Rohm Semiconductor")
        (field (name "MPN") "KTR03EZPF3302")
        (field (name "POWER") "0.1W")
        (field (name "RESISTANCE") "33k")
      )
      (libsource (lib "eagle-import") (part "RESISTOR_?_060333K"))
    )
    (comp (ref "R25")
      (value "RESISTOR_0603_22")
      (footprint "eagle-import:0603-RES")
      (fields
        (field (name "MANUFACTURER") "Yageo")
        (field (name "MPN") "RC0603FR-0722RL")
        (field (name "POWER") "0.1W")
        (field (name "RESISTANCE") "22")
      )
      (libsource (lib "eagle-import") (part "RESISTOR_?_060322"))
    )
    (comp (ref "R26")
      (value "RESISTOR_0603_470")
      (footprint "eagle-import:0603-RES")
      (fields
        (field (name "MANUFACTURER") "Panasonic Electronic Components")
        (field (name "MPN") "ERJ-PA3F4700V")
        (field (name "POWER") "0.25W")
        (field (name "RESISTANCE") "470")
      )
      (libsource (lib "eagle-import") (part "RESISTOR_?_0603470"))
    )
    (comp (ref "R31")
      (value "RESISTOR_0603_470")
      (footprint "eagle-import:0603-RES")
      (fields
        (field (name "MANUFACTURER") "Panasonic Electronic Components")
        (field (name "MPN") "ERJ-PA3F4700V")
        (field (name "POWER") "0.25W")
        (field (name "RESISTANCE") "470")
      )
      (libsource (lib "eagle-import") (part "RESISTOR_?_0603470"))
    )
    (comp (ref "R32")
      (value "RESISTOR_0603_1K")
      (footprint "eagle-import:0603-RES")
      (fields
        (field (name "MANUFACTURER") "TE Connectivity Passive Product")
        (field (name "MPN") " CPF-A-0603B1K0E")
        (field (name "POWER") "0.0625W")
        (field (name "RESISTANCE") "1k")
      )
      (libsource (lib "eagle-import") (part "RESISTOR_?_06031K"))
    )
    (comp (ref "R34")
      (value "RESISTOR_0603_22")
      (footprint "eagle-import:0603-RES")
      (fields
        (field (name "MANUFACTURER") "Yageo")
        (field (name "MPN") "RC0603FR-0722RL")
        (field (name "POWER") "0.1W")
        (field (name "RESISTANCE") "22")
      )
      (libsource (lib "eagle-import") (part "RESISTOR_?_060322"))
    )
    (comp (ref "R35")
      (value "RESISTOR_0603_1K")
      (footprint "eagle-import:0603-RES")
      (fields
        (field (name "MANUFACTURER") "TE Connectivity Passive Product")
        (field (name "MPN") " CPF-A-0603B1K0E")
        (field (name "POWER") "0.0625W")
        (field (name "RESISTANCE") "1k")
      )
      (libsource (lib "eagle-import") (part "RESISTOR_?_06031K"))
    )
    (comp (ref "R37")
      (value "RESISTOR_0603_22")
      (footprint "eagle-import:0603-RES")
      (fields
        (field (name "MANUFACTURER") "Yageo")
        (field (name "MPN") "RC0603FR-0722RL")
        (field (name "POWER") "0.1W")
        (field (name "RESISTANCE") "22")
      )
      (libsource (lib "eagle-import") (part "RESISTOR_?_060322"))
    )
    (comp (ref "R38")
      (value "RESISTOR_0603_2K")
      (footprint "eagle-import:0603-RES")
      (fields
        (field (name "MANUFACTURER") "Panasonic Electronic Components")
        (field (name "MPN") "ERJ-UP3F2001V")
        (field (name "POWER") "0.25W")
        (field (name "RESISTANCE") "2k")
      )
      (libsource (lib "eagle-import") (part "RESISTOR_?_06032K"))
    )
    (comp (ref "SHDN_B")
      (value "LED_0603_ORANGE")
      (footprint "eagle-import:0603-LED")
      (fields
        (field (name "COLOR") "Orange")
        (field (name "MANUFACTURER") "Kingbright")
        (field (name "MPN") "APT1608SECK")
      )
      (libsource (lib "eagle-import") (part "LED_?_0603ORANGE"))
    )
    (comp (ref "SHDN_BTN")
      (value "CONNECTOR-2_μF_T_V_")
      (footprint "eagle-import:MOLEX_MICROFIT_PTH_VERTICAL_02_DUAL")
      (fields (field (name "MANUFACTURER") "Molex") (field (name "MPN") "436500217"))
      (libsource (lib "eagle-import") (part "CONNECTOR-2_?_μF_T_VBLACK"))
    )
    (comp (ref "SHDN_C")
      (value "LED_0603_ORANGE")
      (footprint "eagle-import:0603-LED")
      (fields
        (field (name "COLOR") "Orange")
        (field (name "MANUFACTURER") "Kingbright")
        (field (name "MPN") "APT1608SECK")
      )
      (libsource (lib "eagle-import") (part "LED_?_0603ORANGE"))
    )
    (comp (ref "SHDN_D")
      (value "LED_0603_ORANGE")
      (footprint "eagle-import:0603-LED")
      (fields
        (field (name "COLOR") "Orange")
        (field (name "MANUFACTURER") "Kingbright")
        (field (name "MPN") "APT1608SECK")
      )
      (libsource (lib "eagle-import") (part "LED_?_0603ORANGE"))
    )
    (comp (ref "SHDN_E")
      (value "LED_0603_ORANGE")
      (footprint "eagle-import:0603-LED")
      (fields
        (field (name "COLOR") "Orange")
        (field (name "MANUFACTURER") "Kingbright")
        (field (name "MPN") "APT1608SECK")
      )
      (libsource (lib "eagle-import") (part "LED_?_0603ORANGE"))
    )
    (comp (ref "SHDN_F")
      (value "LED_0603_ORANGE")
      (footprint "eagle-import:0603-LED")
      (fields
        (field (name "COLOR") "Orange")
        (field (name "MANUFACTURER") "Kingbright")
        (field (name "MPN") "APT1608SECK")
      )
      (libsource (lib "eagle-import") (part "LED_?_0603ORANGE"))
    )
    (comp (ref "STATUS_4.0")
      (value "LED_0603_RED")
      (footprint "eagle-import:0603-LED")
      (fields
        (field (name "COLOR") "Red")
        (field (name "MANUFACTURER") "Kingbright")
        (field (name "MPN") "APT1608SECK/J3-PRV")
      )
      (libsource (lib "eagle-import") (part "LED_?_0603RED"))
    )
    (comp (ref "STATUS_4.1")
      (value "LED_0603_RED")
      (footprint "eagle-import:0603-LED")
      (fields
        (field (name "COLOR") "Red")
        (field (name "MANUFACTURER") "Kingbright")
        (field (name "MPN") "APT1608SECK/J3-PRV")
      )
      (libsource (lib "eagle-import") (part "LED_?_0603RED"))
    )
    (comp (ref "TP1")
      (value "TEST_POINT")
      (footprint "eagle-import:5015")
      (fields (field (name "MPN") "5015") (field (name "MANUFACTURER") "Keystone Electronics"))
      (libsource (lib "eagle-import") (part "TEST_POINT"))
    )
    (comp (ref "TP2")
      (value "TEST_POINT")
      (footprint "eagle-import:5015")
      (fields (field (name "MPN") "5015") (field (name "MANUFACTURER") "Keystone Electronics"))
      (libsource (lib "eagle-import") (part "TEST_POINT"))
    )
    (comp (ref "TP3")
      (value "TEST_POINT")
      (footprint "eagle-import:5015")
      (fields (field (name "MPN") "5015") (field (name "MANUFACTURER") "Keystone Electronics"))
      (libsource (lib "eagle-import") (part "TEST_POINT"))
    )
    (comp (ref "TP4")
      (value "TEST_POINT")
      (footprint "eagle-import:5015")
      (fields (field (name "MPN") "5015") (field (name "MANUFACTURER") "Keystone Electronics"))
      (libsource (lib "eagle-import") (part "TEST_POINT"))
    )
    (comp (ref "TP5")
      (value "TEST_POINT")
      (footprint "eagle-import:5015")
      (fields (field (name "MPN") "5015") (field (name "MANUFACTURER") "Keystone Electronics"))
      (libsource (lib "eagle-import") (part "TEST_POINT"))
    )
    (comp (ref "TP6")
      (value "TEST_POINT")
      (footprint "eagle-import:5015")
      (fields (field (name "MPN") "5015") (field (name "MANUFACTURER") "Keystone Electronics"))
      (libsource (lib "eagle-import") (part "TEST_POINT"))
    )
    (comp (ref "TP7")
      (value "TEST_POINT")
      (footprint "eagle-import:5015")
      (fields (field (name "MPN") "5015") (field (name "MANUFACTURER") "Keystone Electronics"))
      (libsource (lib "eagle-import") (part "TEST_POINT"))
    )
    (comp (ref "TP8")
      (value "TEST_POINT")
      (footprint "eagle-import:5015")
      (fields (field (name "MPN") "5015") (field (name "MANUFACTURER") "Keystone Electronics"))
      (libsource (lib "eagle-import") (part "TEST_POINT"))
    )
    (comp (ref "TP9")
      (value "TEST_POINT")
      (footprint "eagle-import:5015")
      (fields (field (name "MPN") "5015") (field (name "MANUFACTURER") "Keystone Electronics"))
      (libsource (lib "eagle-import") (part "TEST_POINT"))
    )
    (comp (ref "TP10")
      (value "TEST_POINT")
      (footprint "eagle-import:5015")
      (fields (field (name "MPN") "5015") (field (name "MANUFACTURER") "Keystone Electronics"))
      (libsource (lib "eagle-import") (part "TEST_POINT"))
    )
    (comp (ref "TP11")
      (value "TEST_POINT")
      (footprint "eagle-import:5015")
      (fields (field (name "MPN") "5015") (field (name "MANUFACTURER") "Keystone Electronics"))
      (libsource (lib "eagle-import") (part "TEST_POINT"))
    )
    (comp (ref "TP12")
      (value "TEST_POINT")
      (footprint "eagle-import:5015")
      (fields (field (name "MPN") "5015") (field (name "MANUFACTURER") "Keystone Electronics"))
      (libsource (lib "eagle-import") (part "TEST_POINT"))
    )
    (comp (ref "TP13")
      (value "TEST_POINT")
      (footprint "eagle-import:5015")
      (fields (field (name "MPN") "5015") (field (name "MANUFACTURER") "Keystone Electronics"))
      (libsource (lib "eagle-import") (part "TEST_POINT"))
    )
    (comp (ref "U$4")
      (value "RELAY_SOLIDSTATE_NO")
      (footprint "eagle-import:DIP-4@1")
      (fields (field (name "MPN") "AQY214EHA") (field (name "MANUFACTURER") "AQY214EHA"))
      (libsource (lib "eagle-import") (part "RELAY_SOLIDSTATE_NO"))
    )
    (comp (ref "R24")
      (value "RESISTOR_0603_1.33K")
      (footprint "eagle-import:0603-RES")
      (fields
        (field (name "MANUFACTURER") "Panasonic Electronic Components")
        (field (name "MPN") "ERA-3AEB1331V")
        (field (name "POWER") "0.1W")
        (field (name "RESISTANCE") "1.33k")
      )
      (libsource (lib "eagle-import") (part "RESISTOR_?_06031.33K"))
    )
    (comp (ref "R33")
      (value "RESISTOR_0603_2.74K")
      (footprint "eagle-import:0603-RES")
      (fields
        (field (name "MANUFACTURER") "Panasonic Electronic Components")
        (field (name "MPN") "ERJ-PB3B2741V")
        (field (name "POWER") "0.2W")
        (field (name "RESISTANCE") "2.74k")
      )
      (libsource (lib "eagle-import") (part "RESISTOR_?_06032.74K"))
    )
  )
  (nets
    (net (code "1") (name "+5V") (class "Default")
      (node (ref "5V_PWR") (pin "2") (pinfunction "A_2") (pintype "passive"))
      (node (ref "A1") (pin "VIN") (pinfunction "VIN_VIN") (pintype "power_in"))
      (node (ref "A2") (pin "VIN") (pinfunction "VIN_VIN") (pintype "power_in"))
      (node (ref "C101") (pin "2") (pinfunction "2_2") (pintype "passive"))
      (node (ref "C103") (pin "2") (pinfunction "2_2") (pintype "passive"))
      (node (ref "C4") (pin "2") (pinfunction "2_2") (pintype "passive"))
      (node (ref "C5") (pin "1") (pinfunction "1_1") (pintype "passive"))
      (node (ref "C6") (pin "1") (pinfunction "1_1") (pintype "passive"))
      (node (ref "LATCH") (pin "2") (pinfunction "A_2") (pintype "passive"))
      (node (ref "TP12") (pin "1") (pinfunction "1_1") (pintype "passive"))
      (node (ref "U3") (pin "3") (pinfunction "OUT_3") (pintype "power_in"))
      (node (ref "U4") (pin "3") (pinfunction "VDD_3") (pintype "power_in"))
      (node (ref "U5") (pin "3") (pinfunction "VDD_3") (pintype "power_in"))
    )
    (net (code "2") (name "+24V") (class "Default")
      (node (ref "C7") (pin "1") (pinfunction "1_1") (pintype "passive"))
      (node (ref "J1") (pin "1") (pinfunction "1_1") (pintype "passive"))
      (node (ref "MAIN_CONNECTOR") (pin "4") (pinfunction "4_4") (pintype "passive"))
      (node (ref "R17") (pin "1") (pinfunction "1_1") (pintype "passive"))
      (node (ref "TP13") (pin "1") (pinfunction "1_1") (pintype "passive"))
      (node (ref "U$4") (pin "4") (pinfunction "CONTACT2_4") (pintype "bidirectional"))
      (node (ref "U3") (pin "1") (pinfunction "IN_1") (pintype "power_in"))
      (node (ref "XF1") (pin "3") (pinfunction "2_3") (pintype "passive"))
      (node (ref "XF1") (pin "4") (pinfunction "2_4") (pintype "passive"))
    )
    (net (code "3") (name "4.0_CRX") (class "Default")
      (node (ref "A2") (pin "D0") (pinfunction "(CRX1)D0_D0") (pintype "bidirectional"))
      (node (ref "A2") (pin "D4") (pinfunction "D4_D4") (pintype "bidirectional"))
      (node (ref "U4") (pin "4") (pinfunction "RXD_4") (pintype "output"))
    )
    (net (code "4") (name "4.0_CTX") (class "Default")
      (node (ref "A2") (pin "D1") (pinfunction "(CTX1)D1_D1") (pintype "bidirectional"))
      (node (ref "A2") (pin "D3") (pinfunction "D3_D3") (pintype "bidirectional"))
      (node (ref "U4") (pin "1") (pinfunction "TXD_1") (pintype "input"))
    )
    (net (code "5") (name "4.1_CRX") (class "Default")
      (node (ref "A1") (pin "D0") (pinfunction "(CRX1)D0_D0") (pintype "bidirectional"))
      (node (ref "A1") (pin "D4") (pinfunction "D4_D4") (pintype "bidirectional"))
      (node (ref "U5") (pin "4") (pinfunction "RXD_4") (pintype "output"))
    )
    (net (code "6") (name "4.1_CTX") (class "Default")
      (node (ref "A1") (pin "D1") (pinfunction "(CTX1)D1_D1") (pintype "bidirectional"))
      (node (ref "A1") (pin "D3") (pinfunction "D3_D3") (pintype "bidirectional"))
      (node (ref "U5") (pin "1") (pinfunction "TXD_1") (pintype "input"))
    )
    (net (code "7") (name "24V_READ") (class "Default")
      (node (ref "A1") (pin "D20") (pinfunction "A6_D20") (pintype "bidirectional"))
      (node (ref "A2") (pin "D20") (pinfunction "A6_D20") (pintype "bidirectional"))
      (node (ref "R10") (pin "1") (pinfunction "1_1") (pintype "passive"))
      (node (ref "R17") (pin "2") (pinfunction "2_2") (pintype "passive"))
    )
    (net (code "8") (name "BMS_OK") (class "Default")
      (node (ref "BMS_OK") (pin "2") (pinfunction "A_2") (pintype "passive"))
      (node (ref "D101") (pin "2") (pinfunction "C_2") (pintype "passive"))
      (node (ref "MAIN_CONNECTOR") (pin "6") (pinfunction "6_6") (pintype "passive"))
      (node (ref "R34") (pin "2") (pinfunction "2_2") (pintype "passive"))
      (node (ref "TP7") (pin "1") (pinfunction "1_1") (pintype "passive"))
    )
    (net (code "9") (name "CANH") (class "Default")
      (node (ref "CAN_TERM") (pin "2") (pinfunction "2_2") (pintype "passive"))
      (node (ref "CHG_CAN") (pin "4") (pinfunction "4_4") (pintype "passive"))
      (node (ref "D100") (pin "1") (pinfunction "C1_1") (pintype "passive"))
      (node (ref "J1") (pin "2") (pinfunction "2_2") (pintype "passive"))
      (node (ref "MAIN_CONNECTOR") (pin "1") (pinfunction "1_1") (pintype "passive"))
      (node (ref "U4") (pin "7") (pinfunction "CANH_7") (pintype "output"))
      (node (ref "U5") (pin "7") (pinfunction "CANH_7") (pintype "output"))
    )
    (net (code "10") (name "CANL") (class "Default")
      (node (ref "CHG_CAN") (pin "5") (pinfunction "5_5") (pintype "passive"))
      (node (ref "D100") (pin "2") (pinfunction "C2_2") (pintype "passive"))
      (node (ref "J1") (pin "3") (pinfunction "3_3") (pintype "passive"))
      (node (ref "MAIN_CONNECTOR") (pin "2") (pinfunction "2_2") (pintype "passive"))
      (node (ref "R40") (pin "1") (pinfunction "1_1") (pintype "passive"))
      (node (ref "U4") (pin "6") (pinfunction "CANL_6") (pintype "bidirectional"))
      (node (ref "U5") (pin "6") (pinfunction "CANL_6") (pintype "bidirectional"))
    )
    (net (code "11") (name "CCU_OK") (class "Default")
      (node (ref "CCU_OK") (pin "2") (pinfunction "A_2") (pintype "passive"))
      (node (ref "R30") (pin "2") (pinfunction "2_2") (pintype "passive"))
      (node (ref "R31") (pin "2") (pinfunction "2_2") (pintype "passive"))
      (node (ref "TP9") (pin "1") (pinfunction "1_1") (pintype "passive"))
      (node (ref "U1") (pin "4") (pinfunction "OUT_4") (pintype "output"))
    )
    (net (code "12") (name "GND") (class "Default")
      (node (ref "A1") (pin "AGND/GND") (pinfunction "GND_AGND/GND") (pintype "bidirectional"))
      (node (ref "A1") (pin "GND") (pinfunction "GND_GND") (pintype "bidirectional"))
      (node (ref "A1") (pin "GND@2") (pinfunction "GND_GND@2") (pintype "bidirectional"))
      (node (ref "A2") (pin "AGND/GND") (pinfunction "GND_AGND/GND") (pintype "power_in"))
      (node (ref "A2") (pin "GND") (pinfunction "GND_GND") (pintype "power_in"))
      (node (ref "C1") (pin "1") (pinfunction "1_1") (pintype "passive"))
      (node (ref "C100") (pin "1") (pinfunction "1_1") (pintype "passive"))
      (node (ref "C101") (pin "1") (pinfunction "1_1") (pintype "passive"))
      (node (ref "C102") (pin "1") (pinfunction "1_1") (pintype "passive"))
      (node (ref "C103") (pin "1") (pinfunction "1_1") (pintype "passive"))
      (node (ref "C2") (pin "1") (pinfunction "1_1") (pintype "passive"))
      (node (ref "C3") (pin "1") (pinfunction "1_1") (pintype "passive"))
      (node (ref "C4") (pin "1") (pinfunction "1_1") (pintype "passive"))
      (node (ref "C5") (pin "2") (pinfunction "2_2") (pintype "passive"))
      (node (ref "C6") (pin "2") (pinfunction "2_2") (pintype "passive"))
      (node (ref "C7") (pin "2") (pinfunction "2_2") (pintype "passive"))
      (node (ref "C8") (pin "2") (pinfunction "2_2") (pintype "passive"))
      (node (ref "CHG_CAN") (pin "6") (pinfunction "6_6") (pintype "passive"))
      (node (ref "D100") (pin "3") (pinfunction "A_3") (pintype "passive"))
      (node (ref "D101") (pin "1") (pinfunction "A_1") (pintype "passive"))
      (node (ref "D102") (pin "1") (pinfunction "A_1") (pintype "passive"))
      (node (ref "D3") (pin "1") (pinfunction "C_1") (pintype "passive"))
      (node (ref "D5") (pin "1") (pinfunction "A_1") (pintype "passive"))
      (node (ref "J1") (pin "4") (pinfunction "4_4") (pintype "passive"))
      (node (ref "K1") (pin "14") (pinfunction "4_14") (pintype "bidirectional"))
      (node (ref "K2") (pin "14") (pinfunction "4_14") (pintype "bidirectional"))
      (node (ref "K3") (pin "14") (pinfunction "4_14") (pintype "bidirectional"))
      (node (ref "LATCH_BUTTON") (pin "3") (pinfunction "S_3") (pintype "passive"))
      (node (ref "LATCH_BUTTON") (pin "4") (pinfunction "S_4") (pintype "passive"))
      (node (ref "MAIN_CONNECTOR") (pin "3") (pinfunction "3_3") (pintype "passive"))
      (node (ref "POWER") (pin "2") (pinfunction "2_2") (pintype "passive"))
      (node (ref "R1") (pin "2") (pinfunction "2_2") (pintype "passive"))
      (node (ref "R10") (pin "2") (pinfunction "2_2") (pintype "passive"))
      (node (ref "R11") (pin "2") (pinfunction "2_2") (pintype "passive"))
      (node (ref "R12") (pin "2") (pinfunction "2_2") (pintype "passive"))
      (node (ref "R13") (pin "2") (pinfunction "2_2") (pintype "passive"))
      (node (ref "R14") (pin "2") (pinfunction "2_2") (pintype "passive"))
      (node (ref "R15") (pin "2") (pinfunction "2_2") (pintype "passive"))
      (node (ref "R16") (pin "2") (pinfunction "2_2") (pintype "passive"))
      (node (ref "R2") (pin "2") (pinfunction "2_2") (pintype "passive"))
      (node (ref "R26") (pin "2") (pinfunction "2_2") (pintype "passive"))
      (node (ref "R27") (pin "2") (pinfunction "2_2") (pintype "passive"))
      (node (ref "R28") (pin "2") (pinfunction "2_2") (pintype "passive"))
      (node (ref "R29") (pin "1") (pinfunction "1_1") (pintype "passive"))
      (node (ref "R30") (pin "1") (pinfunction "1_1") (pintype "passive"))
      (node (ref "R32") (pin "2") (pinfunction "2_2") (pintype "passive"))
      (node (ref "R7") (pin "2") (pinfunction "2_2") (pintype "passive"))
      (node (ref "R8") (pin "2") (pinfunction "2_2") (pintype "passive"))
      (node (ref "R9") (pin "2") (pinfunction "2_2") (pintype "passive"))
      (node (ref "SHDN_B") (pin "1") (pinfunction "C_1") (pintype "passive"))
      (node (ref "SHDN_C") (pin "1") (pinfunction "C_1") (pintype "passive"))
      (node (ref "SHDN_D") (pin "1") (pinfunction "C_1") (pintype "passive"))
      (node (ref "SHDN_E") (pin "1") (pinfunction "C_1") (pintype "passive"))
      (node (ref "TP1") (pin "1") (pinfunction "1_1") (pintype "passive"))
      (node (ref "U$100") (pin "2") (pinfunction "CONTROL-_2") (pintype "passive"))
      (node (ref "U$100") (pin "3") (pinfunction "CONTACT1_3") (pintype "bidirectional"))
      (node (ref "U$4") (pin "2") (pinfunction "CONTROL-_2") (pintype "passive"))
      (node (ref "U1") (pin "3") (pinfunction "GND_3") (pintype "power_in"))
      (node (ref "U2") (pin "2") (pinfunction "GND_2") (pintype "power_in"))
      (node (ref "U3") (pin "2") (pinfunction "GND_2") (pintype "power_in"))
      (node (ref "U4") (pin "2") (pinfunction "GND_2") (pintype "power_in"))
      (node (ref "U4") (pin "8") (pinfunction "S_8") (pintype "input"))
      (node (ref "U5") (pin "2") (pinfunction "GND_2") (pintype "power_in"))
      (node (ref "U5") (pin "8") (pinfunction "S_8") (pintype "input"))
      (node (ref "XB1") (pin "2") (pinfunction "MINUS_2") (pintype "power_in"))
    )
    (net (code "13") (name "IMD_OK") (class "Default")
      (node (ref "D102") (pin "2") (pinfunction "C_2") (pintype "passive"))
      (node (ref "MAIN_CONNECTOR") (pin "5") (pinfunction "5_5") (pintype "passive"))
      (node (ref "OKHS") (pin "2") (pinfunction "A_2") (pintype "passive"))
      (node (ref "R25") (pin "2") (pinfunction "2_2") (pintype "passive"))
      (node (ref "TP8") (pin "1") (pinfunction "1_1") (pintype "passive"))
    )
    (net (code "14") (name "LATCH_BUTTON") (class "Default")
      (node (ref "D1") (pin "C") (pinfunction "C_C") (pintype "passive"))
      (node (ref "D2") (pin "C") (pinfunction "C_C") (pintype "passive"))
      (node (ref "D4") (pin "C") (pinfunction "C_C") (pintype "passive"))
      (node (ref "LATCH_BUTTON") (pin "1") (pinfunction "P_1") (pintype "passive"))
      (node (ref "LATCH_BUTTON") (pin "2") (pinfunction "P_2") (pintype "passive"))
      (node (ref "R35") (pin "2") (pinfunction "2_2") (pintype "passive"))
    )
    (net (code "15") (name "Net-(4.1_ONLY-Pad1)") (class "Default")
      (node (ref "4.1_ONLY") (pin "1") (pinfunction "1_1") (pintype "passive"))
      (node (ref "A1") (pin "3V3") (pinfunction "3.3V_3V3") (pintype "power_in"))
      (node (ref "A1") (pin "3V3@2") (pinfunction "3.3V_3V3@2") (pintype "power_in"))
      (node (ref "A1") (pin "3V3@3") (pinfunction "3.3V_3V3@3") (pintype "power_in"))
    )
    (net (code "16") (name "Net-(5V_PWR-C)") (class "Default")
      (node (ref "5V_PWR") (pin "1") (pinfunction "C_1") (pintype "passive"))
      (node (ref "R32") (pin "1") (pinfunction "1_1") (pintype "passive"))
    )
    (net (code "17") (name "Net-(BMS_OK-C)") (class "Default")
      (node (ref "BMS_OK") (pin "1") (pinfunction "C_1") (pintype "passive"))
      (node (ref "R2") (pin "1") (pinfunction "1_1") (pintype "passive"))
    )
    (net (code "18") (name "Net-(C8-Pad1)") (class "Default")
      (node (ref "C8") (pin "1") (pinfunction "1_1") (pintype "passive"))
      (node (ref "R39") (pin "1") (pinfunction "1_1") (pintype "passive"))
      (node (ref "R40") (pin "2") (pinfunction "2_2") (pintype "passive"))
    )
    (net (code "19") (name "Net-(CAN_TERM-Pad1)") (class "Default")
      (node (ref "CAN_TERM") (pin "1") (pinfunction "1_1") (pintype "passive"))
      (node (ref "R39") (pin "2") (pinfunction "2_2") (pintype "passive"))
    )
    (net (code "20") (name "Net-(CCU_OK-C)") (class "Default")
      (node (ref "CCU_OK") (pin "1") (pinfunction "C_1") (pintype "passive"))
      (node (ref "R9") (pin "1") (pinfunction "1_1") (pintype "passive"))
    )
    (net (code "21") (name "Net-(D3-A)") (class "Default")
      (node (ref "D3") (pin "2") (pinfunction "A_2") (pintype "passive"))
      (node (ref "R38") (pin "2") (pinfunction "2_2") (pintype "passive"))
    )
    (net (code "22") (name "Net-(D5-C)") (class "Default")
      (node (ref "D5") (pin "2") (pinfunction "C_2") (pintype "passive"))
      (node (ref "POWER") (pin "1") (pinfunction "1_1") (pintype "passive"))
      (node (ref "XF1") (pin "1") (pinfunction "1_1") (pintype "passive"))
      (node (ref "XF1") (pin "2") (pinfunction "1_2") (pintype "passive"))
      (node (ref "XF2") (pin "1") (pinfunction "1_1") (pintype "passive"))
      (node (ref "XF2") (pin "2") (pinfunction "1_2") (pintype "passive"))
    )
    (net (code "23") (name "Net-(E_SELECT-Pad2)") (class "Default")
      (node (ref "E_SELECT") (pin "2") (pinfunction "2_2") (pintype "passive"))
      (node (ref "F_SELECT") (pin "2") (pinfunction "2_2") (pintype "passive"))
      (node (ref "R100") (pin "1") (pinfunction "1_1") (pintype "passive"))
    )
    (net (code "24") (name "Net-(K1-3)") (class "Default")
      (node (ref "D1") (pin "A") (pinfunction "A_A") (pintype "passive"))
      (node (ref "D105") (pin "A") (pinfunction "A_A") (pintype "passive"))
      (node (ref "K1") (pin "11") (pinfunction "3_11") (pintype "bidirectional"))
      (node (ref "K1") (pin "A2") (pinfunction "COIL-_A2") (pintype "bidirectional"))
    )
    (net (code "25") (name "Net-(K1-COIL+)") (class "Default")
      (node (ref "D105") (pin "C") (pinfunction "C_C") (pintype "passive"))
      (node (ref "K1") (pin "A1") (pinfunction "COIL+_A1") (pintype "bidirectional"))
      (node (ref "R25") (pin "1") (pinfunction "1_1") (pintype "passive"))
    )
    (net (code "26") (name "Net-(K2-3)") (class "Default")
      (node (ref "D104") (pin "A") (pinfunction "A_A") (pintype "passive"))
      (node (ref "D2") (pin "A") (pinfunction "A_A") (pintype "passive"))
      (node (ref "K2") (pin "11") (pinfunction "3_11") (pintype "bidirectional"))
      (node (ref "K2") (pin "A2") (pinfunction "COIL-_A2") (pintype "bidirectional"))
    )
    (net (code "27") (name "Net-(K2-COIL+)") (class "Default")
      (node (ref "D104") (pin "C") (pinfunction "C_C") (pintype "passive"))
      (node (ref "K2") (pin "A1") (pinfunction "COIL+_A1") (pintype "bidirectional"))
      (node (ref "R34") (pin "1") (pinfunction "1_1") (pintype "passive"))
    )
    (net (code "28") (name "Net-(K3-3)") (class "Default")
      (node (ref "D103") (pin "A") (pinfunction "A_A") (pintype "passive"))
      (node (ref "D4") (pin "A") (pinfunction "A_A") (pintype "passive"))
      (node (ref "K3") (pin "11") (pinfunction "3_11") (pintype "bidirectional"))
      (node (ref "K3") (pin "A2") (pinfunction "COIL-_A2") (pintype "bidirectional"))
    )
    (net (code "29") (name "Net-(K3-COIL+)") (class "Default")
      (node (ref "D103") (pin "C") (pinfunction "C_C") (pintype "passive"))
      (node (ref "K3") (pin "A1") (pinfunction "COIL+_A1") (pintype "bidirectional"))
      (node (ref "R37") (pin "1") (pinfunction "1_1") (pintype "passive"))
    )
    (net (code "30") (name "Net-(LATCH-C)") (class "Default")
      (node (ref "LATCH") (pin "1") (pinfunction "C_1") (pintype "passive"))
      (node (ref "R35") (pin "1") (pinfunction "1_1") (pintype "passive"))
    )
    (net (code "31") (name "Net-(OKHS-C)") (class "Default")
      (node (ref "OKHS") (pin "1") (pinfunction "C_1") (pintype "passive"))
      (node (ref "R7") (pin "1") (pinfunction "1_1") (pintype "passive"))
    )
    (net (code "32") (name "Net-(SHDN_B-A)") (class "Default")
      (node (ref "R3") (pin "2") (pinfunction "2_2") (pintype "passive"))
      (node (ref "SHDN_B") (pin "2") (pinfunction "A_2") (pintype "passive"))
    )
    (net (code "33") (name "Net-(SHDN_C-A)") (class "Default")
      (node (ref "R4") (pin "2") (pinfunction "2_2") (pintype "passive"))
      (node (ref "SHDN_C") (pin "2") (pinfunction "A_2") (pintype "passive"))
    )
    (net (code "34") (name "Net-(SHDN_D-A)") (class "Default")
      (node (ref "R5") (pin "2") (pinfunction "2_2") (pintype "passive"))
      (node (ref "SHDN_D") (pin "2") (pinfunction "A_2") (pintype "passive"))
    )
    (net (code "35") (name "Net-(SHDN_E-A)") (class "Default")
      (node (ref "R6") (pin "2") (pinfunction "2_2") (pintype "passive"))
      (node (ref "SHDN_E") (pin "2") (pinfunction "A_2") (pintype "passive"))
    )
    (net (code "36") (name "Net-(SHDN_F-C)") (class "Default")
      (node (ref "R8") (pin "1") (pinfunction "1_1") (pintype "passive"))
      (node (ref "SHDN_F") (pin "1") (pinfunction "C_1") (pintype "passive"))
    )
    (net (code "37") (name "Net-(STATUS_4.0-C)") (class "Default")
      (node (ref "R26") (pin "1") (pinfunction "1_1") (pintype "passive"))
      (node (ref "STATUS_4.0") (pin "1") (pinfunction "C_1") (pintype "passive"))
    )
    (net (code "38") (name "Net-(STATUS_4.1-C)") (class "Default")
      (node (ref "R1") (pin "1") (pinfunction "1_1") (pintype "passive"))
      (node (ref "STATUS_4.1") (pin "1") (pinfunction "C_1") (pintype "passive"))
    )
    (net (code "39") (name "Net-(U$4-CONTACT1)") (class "Default")
      (node (ref "R37") (pin "2") (pinfunction "2_2") (pintype "passive"))
      (node (ref "R38") (pin "1") (pinfunction "1_1") (pintype "passive"))
      (node (ref "U$4") (pin "3") (pinfunction "CONTACT1_3") (pintype "bidirectional"))
    )
    (net (code "40") (name "Net-(U$4-CONTROL+)") (class "Default")
      (node (ref "R31") (pin "1") (pinfunction "1_1") (pintype "passive"))
      (node (ref "U$4") (pin "1") (pinfunction "CONTROL+_1") (pintype "passive"))
    )
    (net (code "41") (name "Net-(U$100-CONTROL+)") (class "Default")
      (node (ref "R100") (pin "2") (pinfunction "2_2") (pintype "passive"))
      (node (ref "U$100") (pin "1") (pinfunction "CONTROL+_1") (pintype "passive"))
    )
    (net (code "42") (name "Net-(U1A-IN)") (class "Default")
      (node (ref "R27") (pin "1") (pinfunction "1_1") (pintype "passive"))
      (node (ref "U1") (pin "2") (pinfunction "IN_2") (pintype "input"))
      (node (ref "U2") (pin "1") (pinfunction "~{RESET}_1") (pintype "output"))
    )
    (net (code "43") (name "Net-(XB1-PLUS)") (class "Default")
      (node (ref "A1") (pin "VBAT") (pinfunction "VBAT_VBAT") (pintype "power_in"))
      (node (ref "XB1") (pin "1") (pinfunction "PLUS_1") (pintype "power_in"))
    )
    (net (code "44") (name "RPC_SWITCH") (class "Default")
      (node (ref "MAIN_CONNECTOR") (pin "8") (pinfunction "8_8") (pintype "passive"))
      (node (ref "U$100") (pin "4") (pinfunction "CONTACT2_4") (pintype "bidirectional"))
    )
    (net (code "45") (name "SHDN_A") (class "Default")
      (node (ref "K1") (pin "21") (pinfunction "6_21") (pintype "bidirectional"))
      (node (ref "R23") (pin "1") (pinfunction "1_1") (pintype "passive"))
      (node (ref "TP10") (pin "1") (pinfunction "1_1") (pintype "passive"))
      (node (ref "XF2") (pin "3") (pinfunction "2_3") (pintype "passive"))
      (node (ref "XF2") (pin "4") (pinfunction "2_4") (pintype "passive"))
    )
    (net (code "46") (name "SHDN_A_READ") (class "Default")
      (node (ref "A1") (pin "D14") (pinfunction "A0_D14") (pintype "bidirectional"))
      (node (ref "A2") (pin "D14") (pinfunction "A0_D14") (pintype "bidirectional"))
      (node (ref "R16") (pin "1") (pinfunction "1_1") (pintype "passive"))
      (node (ref "R23") (pin "2") (pinfunction "2_2") (pintype "passive"))
    )
    (net (code "47") (name "SHDN_B") (class "Default")
      (node (ref "K1") (pin "24") (pinfunction "5_24") (pintype "bidirectional"))
      (node (ref "K2") (pin "21") (pinfunction "6_21") (pintype "bidirectional"))
      (node (ref "R22") (pin "1") (pinfunction "1_1") (pintype "passive"))
      (node (ref "R3") (pin "1") (pinfunction "1_1") (pintype "passive"))
      (node (ref "TP2") (pin "1") (pinfunction "1_1") (pintype "passive"))
    )
    (net (code "48") (name "SHDN_B_READ") (class "Default")
      (node (ref "A1") (pin "D15") (pinfunction "A1_D15") (pintype "bidirectional"))
      (node (ref "A2") (pin "D15") (pinfunction "A1_D15") (pintype "bidirectional"))
      (node (ref "R15") (pin "1") (pinfunction "1_1") (pintype "passive"))
      (node (ref "R22") (pin "2") (pinfunction "2_2") (pintype "passive"))
    )
    (net (code "49") (name "SHDN_C") (class "Default")
      (node (ref "K2") (pin "24") (pinfunction "5_24") (pintype "bidirectional"))
      (node (ref "K3") (pin "21") (pinfunction "6_21") (pintype "bidirectional"))
      (node (ref "R21") (pin "1") (pinfunction "1_1") (pintype "passive"))
      (node (ref "R4") (pin "1") (pinfunction "1_1") (pintype "passive"))
      (node (ref "TP3") (pin "1") (pinfunction "1_1") (pintype "passive"))
    )
    (net (code "50") (name "SHDN_C_READ") (class "Default")
      (node (ref "A1") (pin "D16") (pinfunction "A2_D16") (pintype "bidirectional"))
      (node (ref "A2") (pin "D16") (pinfunction "A2_D16") (pintype "bidirectional"))
      (node (ref "R14") (pin "1") (pinfunction "1_1") (pintype "passive"))
      (node (ref "R21") (pin "2") (pinfunction "2_2") (pintype "passive"))
    )
    (net (code "51") (name "SHDN_D") (class "Default")
      (node (ref "K3") (pin "24") (pinfunction "5_24") (pintype "bidirectional"))
      (node (ref "R20") (pin "1") (pinfunction "1_1") (pintype "passive"))
      (node (ref "R5") (pin "1") (pinfunction "1_1") (pintype "passive"))
      (node (ref "SHDN_BTN") (pin "1") (pinfunction "1_1") (pintype "passive"))
      (node (ref "TP4") (pin "1") (pinfunction "1_1") (pintype "passive"))
    )
    (net (code "52") (name "SHDN_D_READ") (class "Default")
      (node (ref "A1") (pin "D17") (pinfunction "A3_D17") (pintype "bidirectional"))
      (node (ref "A2") (pin "D17") (pinfunction "A3_D17") (pintype "bidirectional"))
      (node (ref "R13") (pin "1") (pinfunction "1_1") (pintype "passive"))
      (node (ref "R20") (pin "2") (pinfunction "2_2") (pintype "passive"))
    )
    (net (code "53") (name "SHDN_E") (class "Default")
      (node (ref "CHG_CAN") (pin "3") (pinfunction "3_3") (pintype "passive"))
      (node (ref "E_SELECT") (pin "1") (pinfunction "1_1") (pintype "passive"))
      (node (ref "R19") (pin "1") (pinfunction "1_1") (pintype "passive"))
      (node (ref "R6") (pin "1") (pinfunction "1_1") (pintype "passive"))
      (node (ref "SHDN_BTN") (pin "2") (pinfunction "2_2") (pintype "passive"))
      (node (ref "TP5") (pin "1") (pinfunction "1_1") (pintype "passive"))
    )
    (net (code "54") (name "SHDN_E_READ") (class "Default")
      (node (ref "A1") (pin "D18") (pinfunction "A4_D18") (pintype "bidirectional"))
      (node (ref "A2") (pin "D18") (pinfunction "A4_D18") (pintype "bidirectional"))
      (node (ref "R12") (pin "1") (pinfunction "1_1") (pintype "passive"))
      (node (ref "R19") (pin "2") (pinfunction "2_2") (pintype "passive"))
    )
    (net (code "55") (name "SHDN_F") (class "Default")
      (node (ref "CHG_CAN") (pin "1") (pinfunction "1_1") (pintype "passive"))
      (node (ref "CHG_CAN") (pin "2") (pinfunction "2_2") (pintype "passive"))
      (node (ref "F_SELECT") (pin "1") (pinfunction "1_1") (pintype "passive"))
      (node (ref "MAIN_CONNECTOR") (pin "7") (pinfunction "7_7") (pintype "passive"))
      (node (ref "R18") (pin "1") (pinfunction "1_1") (pintype "passive"))
      (node (ref "SHDN_F") (pin "2") (pinfunction "A_2") (pintype "passive"))
      (node (ref "TP6") (pin "1") (pinfunction "1_1") (pintype "passive"))
    )
    (net (code "56") (name "SHDN_F_READ") (class "Default")
      (node (ref "A1") (pin "D19") (pinfunction "A5_D19") (pintype "bidirectional"))
      (node (ref "A2") (pin "D19") (pinfunction "A5_D19") (pintype "bidirectional"))
      (node (ref "R11") (pin "1") (pinfunction "1_1") (pintype "passive"))
      (node (ref "R18") (pin "2") (pinfunction "2_2") (pintype "passive"))
    )
    (net (code "57") (name "STATUS_4.0") (class "Default")
      (node (ref "A2") (pin "D5") (pinfunction "D5_D5") (pintype "bidirectional"))
      (node (ref "STATUS_4.0") (pin "2") (pinfunction "A_2") (pintype "passive"))
    )
    (net (code "58") (name "STATUS_4.1") (class "Default")
      (node (ref "A1") (pin "D5") (pinfunction "D5_D5") (pintype "bidirectional"))
      (node (ref "STATUS_4.1") (pin "2") (pinfunction "A_2") (pintype "passive"))
    )
    (net (code "59") (name "SW_SHUTDOWN") (class "Default")
      (node (ref "A1") (pin "D6") (pinfunction "D6_D6") (pintype "bidirectional"))
      (node (ref "A2") (pin "D6") (pinfunction "D6_D6") (pintype "bidirectional"))
      (node (ref "C1") (pin "2") (pinfunction "2_2") (pintype "passive"))
      (node (ref "R29") (pin "2") (pinfunction "2_2") (pintype "passive"))
      (node (ref "U2") (pin "3") (pinfunction "~{MR}_3") (pintype "input"))
    )
    (net (code "60") (name "VDD") (class "Default")
      (node (ref "4.1_ONLY") (pin "2") (pinfunction "2_2") (pintype "passive"))
      (node (ref "A2") (pin "3.3V") (pinfunction "3.3V_3.3V") (pintype "power_in"))
      (node (ref "C100") (pin "2") (pinfunction "2_2") (pintype "passive"))
      (node (ref "C102") (pin "2") (pinfunction "2_2") (pintype "passive"))
      (node (ref "C2") (pin "2") (pinfunction "2_2") (pintype "passive"))
      (node (ref "C3") (pin "2") (pinfunction "2_2") (pintype "passive"))
      (node (ref "TP11") (pin "1") (pinfunction "1_1") (pintype "passive"))
      (node (ref "U1") (pin "5") (pinfunction "VDD_5") (pintype "power_in"))
      (node (ref "U2") (pin "5") (pinfunction "VDD_5") (pintype "power_in"))
      (node (ref "U4") (pin "5") (pinfunction "VIO_5") (pintype "power_in"))
      (node (ref "U5") (pin "5") (pinfunction "VIO_5") (pintype "power_in"))
    )
    (net (code "61") (name "WATCHDOG_IN") (class "Default")
      (node (ref "A1") (pin "D7") (pinfunction "D7_D7") (pintype "bidirectional"))
      (node (ref "A2") (pin "D7") (pinfunction "D7_D7") (pintype "bidirectional"))
      (node (ref "R28") (pin "1") (pinfunction "1_1") (pintype "passive"))
      (node (ref "U2") (pin "4") (pinfunction "WDI_4") (pintype "input"))
    )
    (net (code "62") (name "unconnected-(A1-(CLK)D13-PadD13)") (class "Default")
      (node (ref "A1") (pin "D13") (pinfunction "(CLK)D13_D13") (pintype "bidirectional"))
    )
    (net (code "63") (name "unconnected-(A1-(CS)D10-PadD10)") (class "Default")
      (node (ref "A1") (pin "D10") (pinfunction "(CS)D10_D10") (pintype "bidirectional"))
    )
    (net (code "64") (name "unconnected-(A1-(SDI)D12-PadD12)") (class "Default")
      (node (ref "A1") (pin "D12") (pinfunction "(SDI)D12_D12") (pintype "bidirectional"))
    )
    (net (code "65") (name "unconnected-(A1-(SDO)D11-PadD11)") (class "Default")
      (node (ref "A1") (pin "D11") (pinfunction "(SDO)D11_D11") (pintype "bidirectional"))
    )
    (net (code "66") (name "unconnected-(A1-A7-PadD21)") (class "Default")
      (node (ref "A1") (pin "D21") (pinfunction "A7_D21") (pintype "bidirectional"))
    )
    (net (code "67") (name "unconnected-(A1-A8-PadD22)") (class "Default")
      (node (ref "A1") (pin "D22") (pinfunction "A8_D22") (pintype "bidirectional"))
    )
    (net (code "68") (name "unconnected-(A1-A9-PadD23)") (class "Default")
      (node (ref "A1") (pin "D23") (pinfunction "A9_D23") (pintype "bidirectional"))
    )
    (net (code "69") (name "unconnected-(A1-A10-PadD24)") (class "Default")
      (node (ref "A1") (pin "D24") (pinfunction "A10_D24") (pintype "bidirectional"))
    )
    (net (code "70") (name "unconnected-(A1-A11-PadD25)") (class "Default")
      (node (ref "A1") (pin "D25") (pinfunction "A11_D25") (pintype "bidirectional"))
    )
    (net (code "71") (name "unconnected-(A1-A12-PadD26)") (class "Default")
      (node (ref "A1") (pin "D26") (pinfunction "A12_D26") (pintype "bidirectional"))
    )
    (net (code "72") (name "unconnected-(A1-A13-PadD27)") (class "Default")
      (node (ref "A1") (pin "D27") (pinfunction "A13_D27") (pintype "bidirectional"))
    )
    (net (code "73") (name "unconnected-(A1-A14-PadD38)") (class "Default")
      (node (ref "A1") (pin "D38") (pinfunction "A14_D38") (pintype "bidirectional"))
    )
    (net (code "74") (name "unconnected-(A1-A15-PadD39)") (class "Default")
      (node (ref "A1") (pin "D39") (pinfunction "A15_D39") (pintype "bidirectional"))
    )
    (net (code "75") (name "unconnected-(A1-A16-PadD40)") (class "Default")
      (node (ref "A1") (pin "D40") (pinfunction "A16_D40") (pintype "bidirectional"))
    )
    (net (code "76") (name "unconnected-(A1-A17-PadD41)") (class "Default")
      (node (ref "A1") (pin "D41") (pinfunction "A17_D41") (pintype "bidirectional"))
    )
    (net (code "77") (name "unconnected-(A1-PadD2)") (class "Default")
      (node (ref "A1") (pin "D2") (pinfunction "D2_D2") (pintype "bidirectional"))
    )
    (net (code "78") (name "unconnected-(A1-PadD8)") (class "Default")
      (node (ref "A1") (pin "D8") (pinfunction "D8_D8") (pintype "bidirectional"))
    )
    (net (code "79") (name "unconnected-(A1-PadD9)") (class "Default")
      (node (ref "A1") (pin "D9") (pinfunction "D9_D9") (pintype "bidirectional"))
    )
    (net (code "80") (name "unconnected-(A1-PadD28)") (class "Default")
      (node (ref "A1") (pin "D28") (pinfunction "D28_D28") (pintype "bidirectional"))
    )
    (net (code "81") (name "unconnected-(A1-PadD29)") (class "Default")
      (node (ref "A1") (pin "D29") (pinfunction "D29_D29") (pintype "bidirectional"))
    )
    (net (code "82") (name "unconnected-(A1-PadD30)") (class "Default")
      (node (ref "A1") (pin "D30") (pinfunction "D30_D30") (pintype "bidirectional"))
    )
    (net (code "83") (name "unconnected-(A1-PadD31)") (class "Default")
      (node (ref "A1") (pin "D31") (pinfunction "D31_D31") (pintype "bidirectional"))
    )
    (net (code "84") (name "unconnected-(A1-PadD32)") (class "Default")
      (node (ref "A1") (pin "D32") (pinfunction "D32_D32") (pintype "bidirectional"))
    )
    (net (code "85") (name "unconnected-(A1-PadD33)") (class "Default")
      (node (ref "A1") (pin "D33") (pinfunction "D33_D33") (pintype "bidirectional"))
    )
    (net (code "86") (name "unconnected-(A1-PadD34)") (class "Default")
      (node (ref "A1") (pin "D34") (pinfunction "D34_D34") (pintype "bidirectional"))
    )
    (net (code "87") (name "unconnected-(A1-PadD35)") (class "Default")
      (node (ref "A1") (pin "D35") (pinfunction "D35_D35") (pintype "bidirectional"))
    )
    (net (code "88") (name "unconnected-(A1-PadD36)") (class "Default")
      (node (ref "A1") (pin "D36") (pinfunction "D36_D36") (pintype "bidirectional"))
    )
    (net (code "89") (name "unconnected-(A1-PadD37)") (class "Default")
      (node (ref "A1") (pin "D37") (pinfunction "D37_D37") (pintype "bidirectional"))
    )
    (net (code "90") (name "unconnected-(A2-(CLK)D13-PadD13)") (class "Default")
      (node (ref "A2") (pin "D13") (pinfunction "(CLK)D13_D13") (pintype "bidirectional"))
    )
    (net (code "91") (name "unconnected-(A2-(CS)D10-PadD10)") (class "Default")
      (node (ref "A2") (pin "D10") (pinfunction "(CS)D10_D10") (pintype "bidirectional"))
    )
    (net (code "92") (name "unconnected-(A2-(SDI)D12-PadD12)") (class "Default")
      (node (ref "A2") (pin "D12") (pinfunction "(SDI)D12_D12") (pintype "bidirectional"))
    )
    (net (code "93") (name "unconnected-(A2-(SDO)D11-PadD11)") (class "Default")
      (node (ref "A2") (pin "D11") (pinfunction "(SDO)D11_D11") (pintype "bidirectional"))
    )
    (net (code "94") (name "unconnected-(A2-A7-PadD21)") (class "Default")
      (node (ref "A2") (pin "D21") (pinfunction "A7_D21") (pintype "bidirectional"))
    )
    (net (code "95") (name "unconnected-(A2-A8-PadD22)") (class "Default")
      (node (ref "A2") (pin "D22") (pinfunction "A8_D22") (pintype "bidirectional"))
    )
    (net (code "96") (name "unconnected-(A2-A9-PadD23)") (class "Default")
      (node (ref "A2") (pin "D23") (pinfunction "A9_D23") (pintype "bidirectional"))
    )
    (net (code "97") (name "unconnected-(A2-PadD2)") (class "Default")
      (node (ref "A2") (pin "D2") (pinfunction "D2_D2") (pintype "bidirectional"))
    )
    (net (code "98") (name "unconnected-(A2-PadD8)") (class "Default")
      (node (ref "A2") (pin "D8") (pinfunction "D8_D8") (pintype "bidirectional"))
    )
    (net (code "99") (name "unconnected-(A2-PadD9)") (class "Default")
      (node (ref "A2") (pin "D9") (pinfunction "D9_D9") (pintype "bidirectional"))
    )
    (net (code "100") (name "unconnected-(K1-2-Pad12)") (class "Default")
      (node (ref "K1") (pin "12") (pinfunction "2_12") (pintype "bidirectional"))
    )
    (net (code "101") (name "unconnected-(K1-7-Pad22)") (class "Default")
      (node (ref "K1") (pin "22") (pinfunction "7_22") (pintype "bidirectional"))
    )
    (net (code "102") (name "unconnected-(K2-2-Pad12)") (class "Default")
      (node (ref "K2") (pin "12") (pinfunction "2_12") (pintype "bidirectional"))
    )
    (net (code "103") (name "unconnected-(K2-7-Pad22)") (class "Default")
      (node (ref "K2") (pin "22") (pinfunction "7_22") (pintype "bidirectional"))
    )
    (net (code "104") (name "unconnected-(K3-2-Pad12)") (class "Default")
      (node (ref "K3") (pin "12") (pinfunction "2_12") (pintype "bidirectional"))
    )
    (net (code "105") (name "unconnected-(K3-7-Pad22)") (class "Default")
      (node (ref "K3") (pin "22") (pinfunction "7_22") (pintype "bidirectional"))
    )
    (net (code "106") (name "unconnected-(R24-Pad1)") (class "Default")
      (node (ref "R24") (pin "1") (pinfunction "1_1") (pintype "passive"))
    )
    (net (code "107") (name "unconnected-(R24-Pad2)") (class "Default")
      (node (ref "R24") (pin "2") (pinfunction "2_2") (pintype "passive"))
    )
    (net (code "108") (name "unconnected-(R33-Pad1)") (class "Default")
      (node (ref "R33") (pin "1") (pinfunction "1_1") (pintype "passive"))
    )
    (net (code "109") (name "unconnected-(R33-Pad2)") (class "Default")
      (node (ref "R33") (pin "2") (pinfunction "2_2") (pintype "passive"))
    )
  )
)
